# 10X_SD_CARD_READER_SCH_SHEET_3.net
KiCad netlist of a schematic drawn in Altium Designer
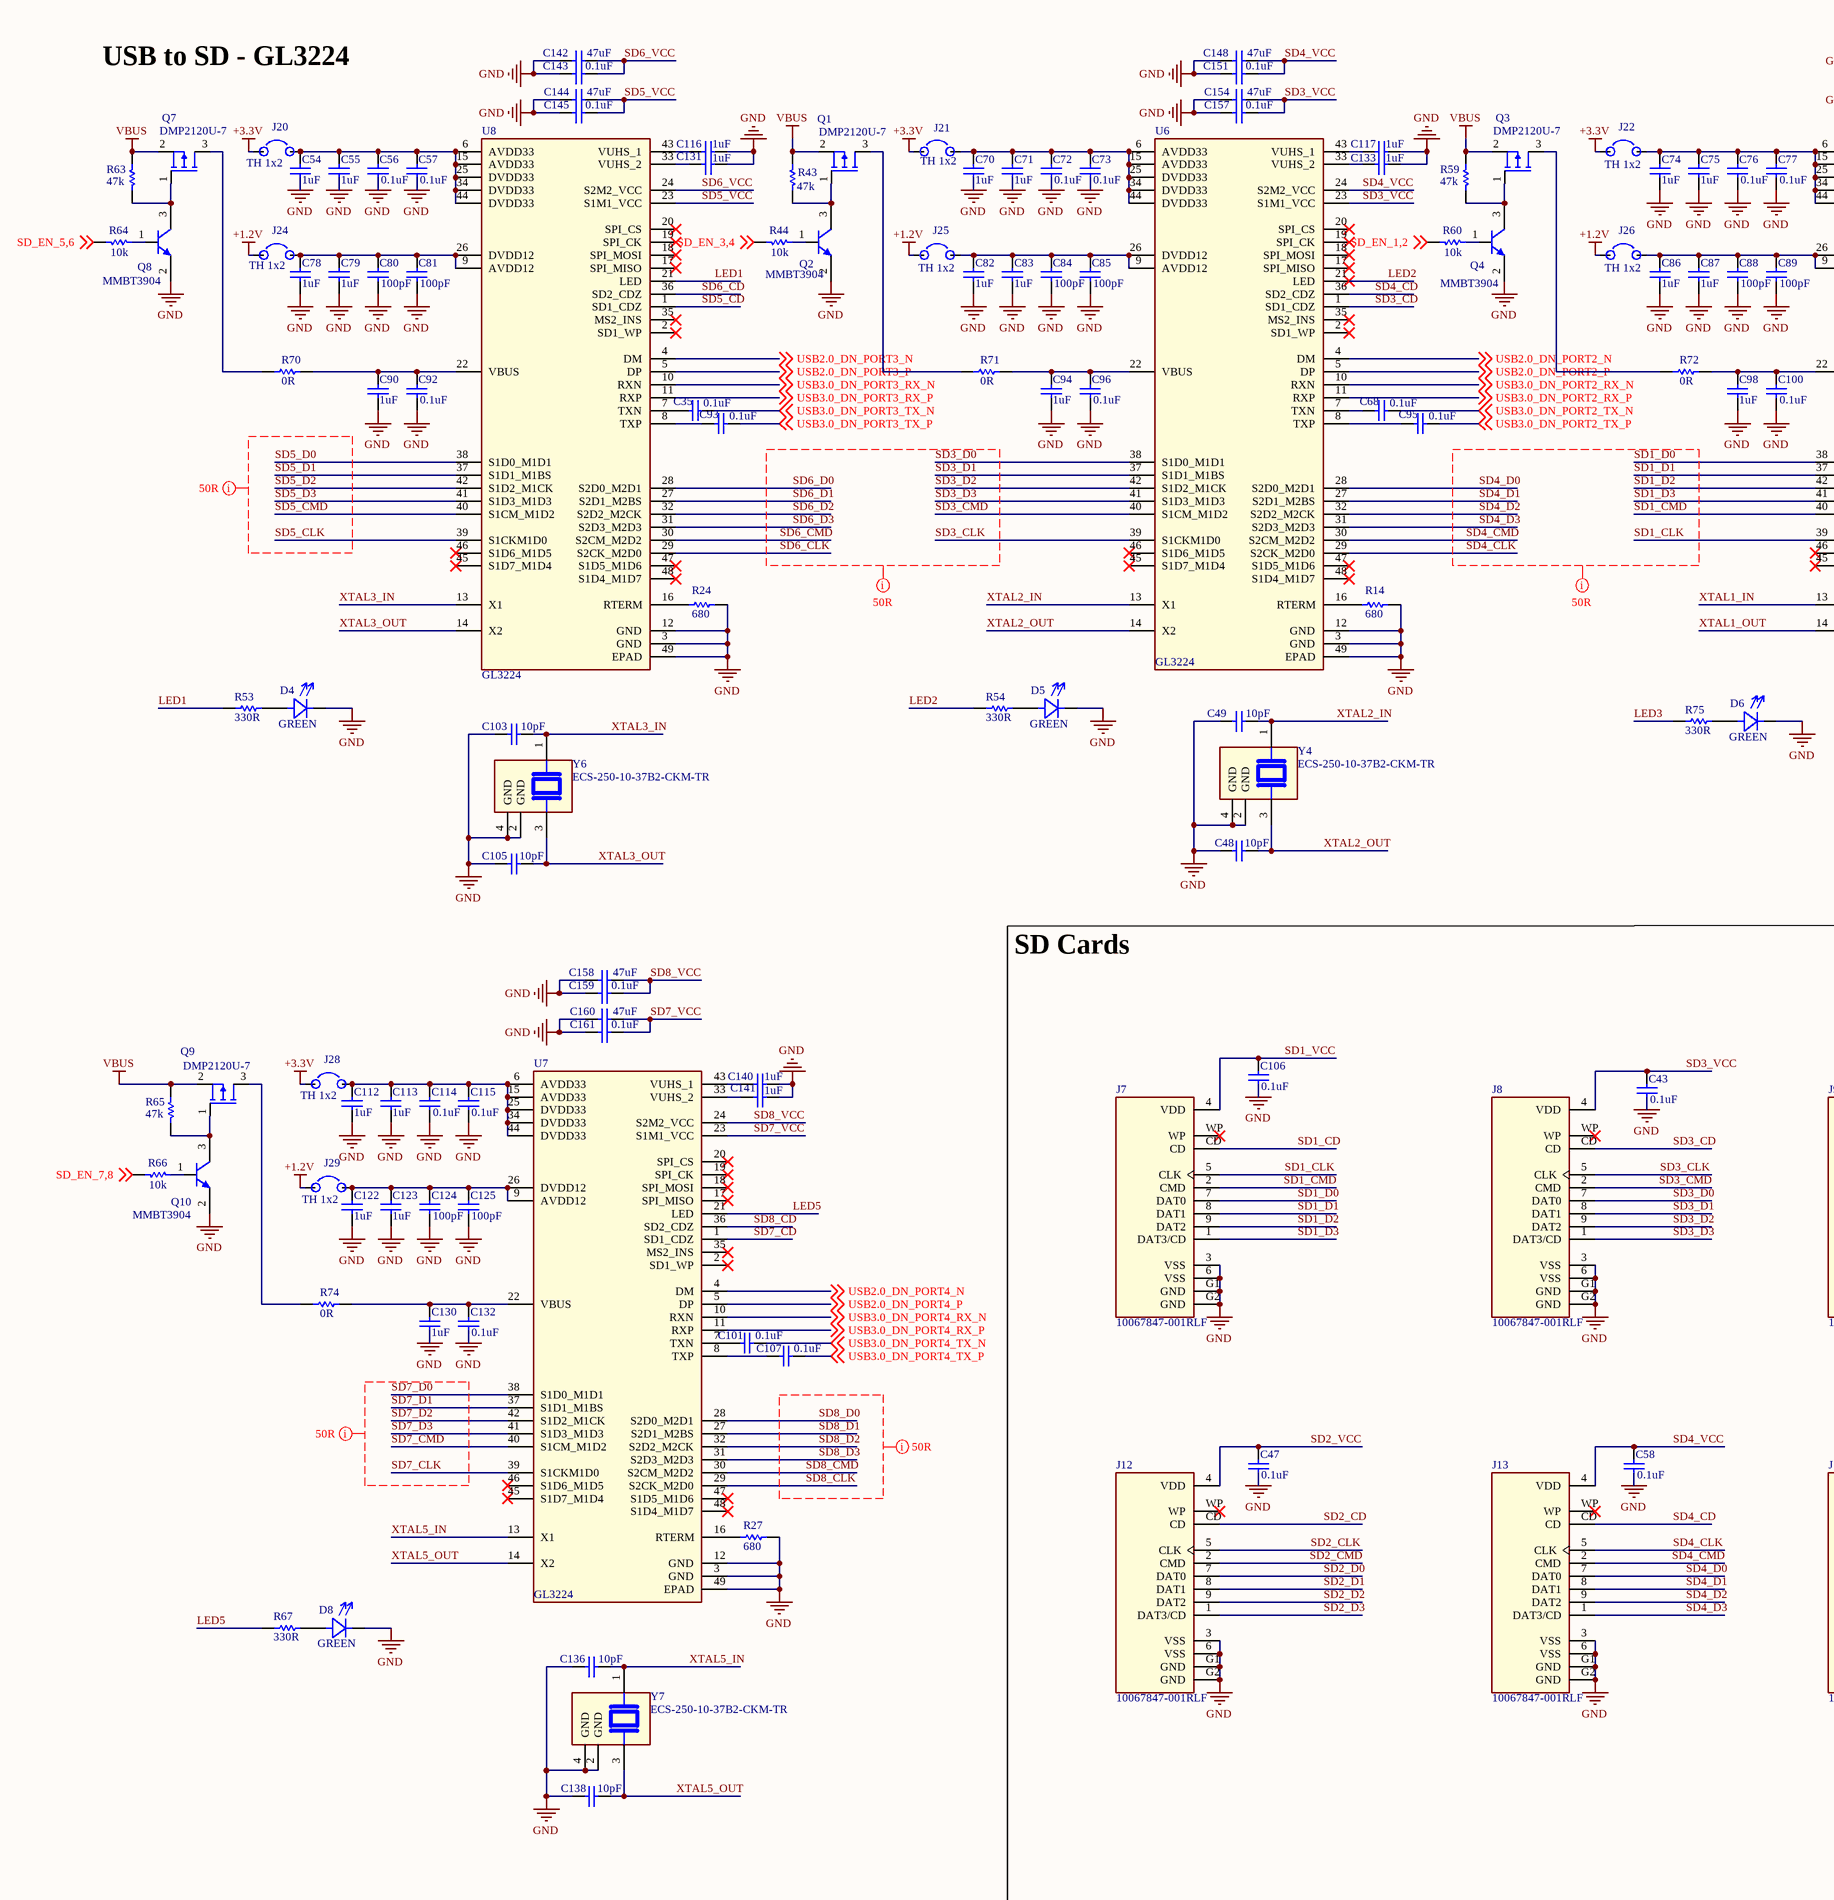
[diagram p0: 10X SD CARD READER SCH SHEET 3.SchDoc, left]
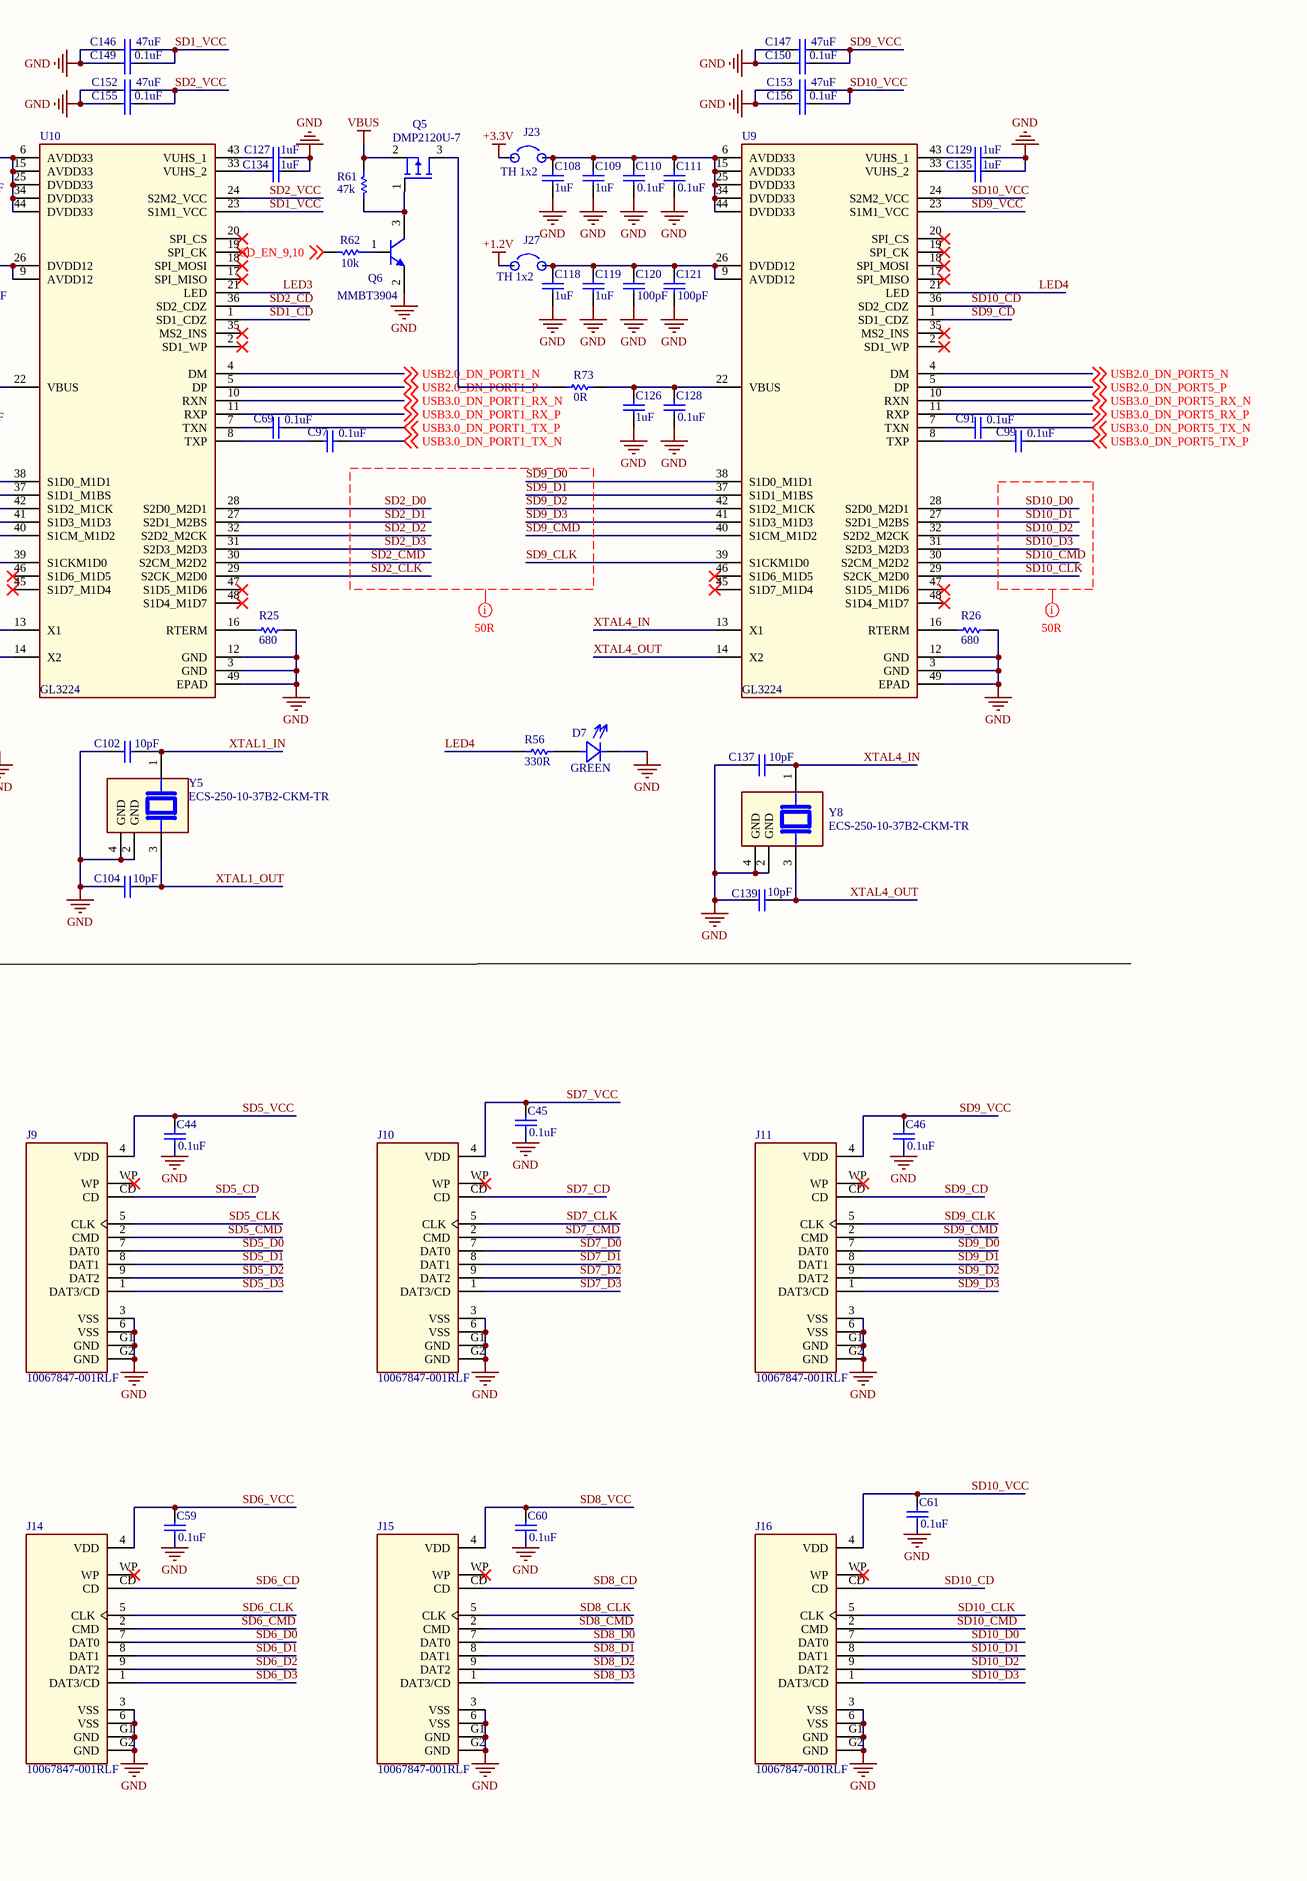
[diagram p1: 10X SD CARD READER SCH SHEET 3.SchDoc, right]

(export (version "E")
  (design (tool "Eeschema 10.0.6"))
  (components
    (comp (ref "C35")
      (value "0.1uF")
      (footprint "C-0402/1005")
      (description "Capacitor")
      (fields (field (name "PUBLISHER") "Altium Limited"))
      (libsource (lib "Miscellaneous Devices") (part "Cap"))
    )
    (comp (ref "C43")
      (value "0.1uF")
      (footprint "C-0402/1005")
      (description "Capacitor")
      (fields (field (name "PUBLISHER") "Altium Limited"))
      (libsource (lib "Miscellaneous Devices") (part "Cap"))
    )
    (comp (ref "C44")
      (value "0.1uF")
      (footprint "C-0402/1005")
      (description "Capacitor")
      (fields (field (name "PUBLISHER") "Altium Limited"))
      (libsource (lib "Miscellaneous Devices") (part "Cap"))
    )
    (comp (ref "C45")
      (value "0.1uF")
      (footprint "C-0402/1005")
      (description "Capacitor")
      (fields (field (name "PUBLISHER") "Altium Limited"))
      (libsource (lib "Miscellaneous Devices") (part "Cap"))
    )
    (comp (ref "C46")
      (value "0.1uF")
      (footprint "C-0402/1005")
      (description "Capacitor")
      (fields (field (name "PUBLISHER") "Altium Limited"))
      (libsource (lib "Miscellaneous Devices") (part "Cap"))
    )
    (comp (ref "C47")
      (value "0.1uF")
      (footprint "C-0402/1005")
      (description "Capacitor")
      (fields (field (name "PUBLISHER") "Altium Limited"))
      (libsource (lib "Miscellaneous Devices") (part "Cap"))
    )
    (comp (ref "C48")
      (value "10pF")
      (footprint "C-0402/1005")
      (description "Capacitor")
      (fields (field (name "PUBLISHER") "Altium Limited"))
      (libsource (lib "Miscellaneous Devices") (part "Cap"))
    )
    (comp (ref "C49")
      (value "10pF")
      (footprint "C-0402/1005")
      (description "Capacitor")
      (fields (field (name "PUBLISHER") "Altium Limited"))
      (libsource (lib "Miscellaneous Devices") (part "Cap"))
    )
    (comp (ref "C54")
      (value "1uF")
      (footprint "C-0402/1005")
      (description "Capacitor")
      (fields (field (name "PUBLISHER") "Altium Limited"))
      (libsource (lib "Miscellaneous Devices") (part "Cap"))
    )
    (comp (ref "C55")
      (value "1uF")
      (footprint "C-0402/1005")
      (description "Capacitor")
      (fields (field (name "PUBLISHER") "Altium Limited"))
      (libsource (lib "Miscellaneous Devices") (part "Cap"))
    )
    (comp (ref "C56")
      (value "0.1uF")
      (footprint "C-0402/1005")
      (description "Capacitor")
      (fields (field (name "PUBLISHER") "Altium Limited"))
      (libsource (lib "Miscellaneous Devices") (part "Cap"))
    )
    (comp (ref "C57")
      (value "0.1uF")
      (footprint "C-0402/1005")
      (description "Capacitor")
      (fields (field (name "PUBLISHER") "Altium Limited"))
      (libsource (lib "Miscellaneous Devices") (part "Cap"))
    )
    (comp (ref "C58")
      (value "0.1uF")
      (footprint "C-0402/1005")
      (description "Capacitor")
      (fields (field (name "PUBLISHER") "Altium Limited"))
      (libsource (lib "Miscellaneous Devices") (part "Cap"))
    )
    (comp (ref "C59")
      (value "0.1uF")
      (footprint "C-0402/1005")
      (description "Capacitor")
      (fields (field (name "PUBLISHER") "Altium Limited"))
      (libsource (lib "Miscellaneous Devices") (part "Cap"))
    )
    (comp (ref "C60")
      (value "0.1uF")
      (footprint "C-0402/1005")
      (description "Capacitor")
      (fields (field (name "PUBLISHER") "Altium Limited"))
      (libsource (lib "Miscellaneous Devices") (part "Cap"))
    )
    (comp (ref "C61")
      (value "0.1uF")
      (footprint "C-0402/1005")
      (description "Capacitor")
      (fields (field (name "PUBLISHER") "Altium Limited"))
      (libsource (lib "Miscellaneous Devices") (part "Cap"))
    )
    (comp (ref "C68")
      (value "0.1uF")
      (footprint "C-0402/1005")
      (description "Capacitor")
      (fields (field (name "PUBLISHER") "Altium Limited"))
      (libsource (lib "Miscellaneous Devices") (part "Cap"))
    )
    (comp (ref "C69")
      (value "0.1uF")
      (footprint "C-0402/1005")
      (description "Capacitor")
      (fields (field (name "PUBLISHER") "Altium Limited"))
      (libsource (lib "Miscellaneous Devices") (part "Cap"))
    )
    (comp (ref "C70")
      (value "1uF")
      (footprint "C-0402/1005")
      (description "Capacitor")
      (fields (field (name "PUBLISHER") "Altium Limited"))
      (libsource (lib "Miscellaneous Devices") (part "Cap"))
    )
    (comp (ref "C71")
      (value "1uF")
      (footprint "C-0402/1005")
      (description "Capacitor")
      (fields (field (name "PUBLISHER") "Altium Limited"))
      (libsource (lib "Miscellaneous Devices") (part "Cap"))
    )
    (comp (ref "C72")
      (value "0.1uF")
      (footprint "C-0402/1005")
      (description "Capacitor")
      (fields (field (name "PUBLISHER") "Altium Limited"))
      (libsource (lib "Miscellaneous Devices") (part "Cap"))
    )
    (comp (ref "C73")
      (value "0.1uF")
      (footprint "C-0402/1005")
      (description "Capacitor")
      (fields (field (name "PUBLISHER") "Altium Limited"))
      (libsource (lib "Miscellaneous Devices") (part "Cap"))
    )
    (comp (ref "C74")
      (value "1uF")
      (footprint "C-0402/1005")
      (description "Capacitor")
      (fields (field (name "PUBLISHER") "Altium Limited"))
      (libsource (lib "Miscellaneous Devices") (part "Cap"))
    )
    (comp (ref "C75")
      (value "1uF")
      (footprint "C-0402/1005")
      (description "Capacitor")
      (fields (field (name "PUBLISHER") "Altium Limited"))
      (libsource (lib "Miscellaneous Devices") (part "Cap"))
    )
    (comp (ref "C76")
      (value "0.1uF")
      (footprint "C-0402/1005")
      (description "Capacitor")
      (fields (field (name "PUBLISHER") "Altium Limited"))
      (libsource (lib "Miscellaneous Devices") (part "Cap"))
    )
    (comp (ref "C77")
      (value "0.1uF")
      (footprint "C-0402/1005")
      (description "Capacitor")
      (fields (field (name "PUBLISHER") "Altium Limited"))
      (libsource (lib "Miscellaneous Devices") (part "Cap"))
    )
    (comp (ref "C78")
      (value "1uF")
      (footprint "C-0402/1005")
      (description "Capacitor")
      (fields (field (name "PUBLISHER") "Altium Limited"))
      (libsource (lib "Miscellaneous Devices") (part "Cap"))
    )
    (comp (ref "C79")
      (value "1uF")
      (footprint "C-0402/1005")
      (description "Capacitor")
      (fields (field (name "PUBLISHER") "Altium Limited"))
      (libsource (lib "Miscellaneous Devices") (part "Cap"))
    )
    (comp (ref "C80")
      (value "100pF")
      (footprint "C-0402/1005")
      (description "Capacitor")
      (fields (field (name "Comment") "0.1uF") (field (name "PUBLISHER") "Altium Limited"))
      (libsource (lib "Miscellaneous Devices") (part "Cap"))
    )
    (comp (ref "C81")
      (value "100pF")
      (footprint "C-0402/1005")
      (description "Capacitor")
      (fields (field (name "Comment") "0.1uF") (field (name "PUBLISHER") "Altium Limited"))
      (libsource (lib "Miscellaneous Devices") (part "Cap"))
    )
    (comp (ref "C82")
      (value "1uF")
      (footprint "C-0402/1005")
      (description "Capacitor")
      (fields (field (name "PUBLISHER") "Altium Limited"))
      (libsource (lib "Miscellaneous Devices") (part "Cap"))
    )
    (comp (ref "C83")
      (value "1uF")
      (footprint "C-0402/1005")
      (description "Capacitor")
      (fields (field (name "PUBLISHER") "Altium Limited"))
      (libsource (lib "Miscellaneous Devices") (part "Cap"))
    )
    (comp (ref "C84")
      (value "100pF")
      (footprint "C-0402/1005")
      (description "Capacitor")
      (fields (field (name "Comment") "0.1uF") (field (name "PUBLISHER") "Altium Limited"))
      (libsource (lib "Miscellaneous Devices") (part "Cap"))
    )
    (comp (ref "C85")
      (value "100pF")
      (footprint "C-0402/1005")
      (description "Capacitor")
      (fields (field (name "Comment") "0.1uF") (field (name "PUBLISHER") "Altium Limited"))
      (libsource (lib "Miscellaneous Devices") (part "Cap"))
    )
    (comp (ref "C86")
      (value "1uF")
      (footprint "C-0402/1005")
      (description "Capacitor")
      (fields (field (name "PUBLISHER") "Altium Limited"))
      (libsource (lib "Miscellaneous Devices") (part "Cap"))
    )
    (comp (ref "C87")
      (value "1uF")
      (footprint "C-0402/1005")
      (description "Capacitor")
      (fields (field (name "PUBLISHER") "Altium Limited"))
      (libsource (lib "Miscellaneous Devices") (part "Cap"))
    )
    (comp (ref "C88")
      (value "100pF")
      (footprint "C-0402/1005")
      (description "Capacitor")
      (fields (field (name "Comment") "0.1uF") (field (name "PUBLISHER") "Altium Limited"))
      (libsource (lib "Miscellaneous Devices") (part "Cap"))
    )
    (comp (ref "C89")
      (value "100pF")
      (footprint "C-0402/1005")
      (description "Capacitor")
      (fields (field (name "Comment") "0.1uF") (field (name "PUBLISHER") "Altium Limited"))
      (libsource (lib "Miscellaneous Devices") (part "Cap"))
    )
    (comp (ref "C90")
      (value "1uF")
      (footprint "C-0402/1005")
      (description "Capacitor")
      (fields (field (name "PUBLISHER") "Altium Limited"))
      (libsource (lib "Miscellaneous Devices") (part "Cap"))
    )
    (comp (ref "C91")
      (value "0.1uF")
      (footprint "C-0402/1005")
      (description "Capacitor")
      (fields (field (name "PUBLISHER") "Altium Limited"))
      (libsource (lib "Miscellaneous Devices") (part "Cap"))
    )
    (comp (ref "C92")
      (value "0.1uF")
      (footprint "C-0402/1005")
      (description "Capacitor")
      (fields (field (name "PUBLISHER") "Altium Limited"))
      (libsource (lib "Miscellaneous Devices") (part "Cap"))
    )
    (comp (ref "C93")
      (value "0.1uF")
      (footprint "C-0402/1005")
      (description "Capacitor")
      (fields (field (name "PUBLISHER") "Altium Limited"))
      (libsource (lib "Miscellaneous Devices") (part "Cap"))
    )
    (comp (ref "C94")
      (value "1uF")
      (footprint "C-0402/1005")
      (description "Capacitor")
      (fields (field (name "PUBLISHER") "Altium Limited"))
      (libsource (lib "Miscellaneous Devices") (part "Cap"))
    )
    (comp (ref "C95")
      (value "0.1uF")
      (footprint "C-0402/1005")
      (description "Capacitor")
      (fields (field (name "PUBLISHER") "Altium Limited"))
      (libsource (lib "Miscellaneous Devices") (part "Cap"))
    )
    (comp (ref "C96")
      (value "0.1uF")
      (footprint "C-0402/1005")
      (description "Capacitor")
      (fields (field (name "PUBLISHER") "Altium Limited"))
      (libsource (lib "Miscellaneous Devices") (part "Cap"))
    )
    (comp (ref "C97")
      (value "0.1uF")
      (footprint "C-0402/1005")
      (description "Capacitor")
      (fields (field (name "PUBLISHER") "Altium Limited"))
      (libsource (lib "Miscellaneous Devices") (part "Cap"))
    )
    (comp (ref "C98")
      (value "1uF")
      (footprint "C-0402/1005")
      (description "Capacitor")
      (fields (field (name "PUBLISHER") "Altium Limited"))
      (libsource (lib "Miscellaneous Devices") (part "Cap"))
    )
    (comp (ref "C99")
      (value "0.1uF")
      (footprint "C-0402/1005")
      (description "Capacitor")
      (fields (field (name "PUBLISHER") "Altium Limited"))
      (libsource (lib "Miscellaneous Devices") (part "Cap"))
    )
    (comp (ref "C100")
      (value "0.1uF")
      (footprint "C-0402/1005")
      (description "Capacitor")
      (fields (field (name "PUBLISHER") "Altium Limited"))
      (libsource (lib "Miscellaneous Devices") (part "Cap"))
    )
    (comp (ref "C101")
      (value "0.1uF")
      (footprint "C-0402/1005")
      (description "Capacitor")
      (fields (field (name "PUBLISHER") "Altium Limited"))
      (libsource (lib "Miscellaneous Devices") (part "Cap"))
    )
    (comp (ref "C102")
      (value "10pF")
      (footprint "C-0402/1005")
      (description "Capacitor")
      (fields (field (name "PUBLISHER") "Altium Limited"))
      (libsource (lib "Miscellaneous Devices") (part "Cap"))
    )
    (comp (ref "C103")
      (value "10pF")
      (footprint "C-0402/1005")
      (description "Capacitor")
      (fields (field (name "PUBLISHER") "Altium Limited"))
      (libsource (lib "Miscellaneous Devices") (part "Cap"))
    )
    (comp (ref "C104")
      (value "10pF")
      (footprint "C-0402/1005")
      (description "Capacitor")
      (fields (field (name "PUBLISHER") "Altium Limited"))
      (libsource (lib "Miscellaneous Devices") (part "Cap"))
    )
    (comp (ref "C105")
      (value "10pF")
      (footprint "C-0402/1005")
      (description "Capacitor")
      (fields (field (name "PUBLISHER") "Altium Limited"))
      (libsource (lib "Miscellaneous Devices") (part "Cap"))
    )
    (comp (ref "C106")
      (value "0.1uF")
      (footprint "C-0402/1005")
      (description "Capacitor")
      (fields (field (name "PUBLISHER") "Altium Limited"))
      (libsource (lib "Miscellaneous Devices") (part "Cap"))
    )
    (comp (ref "C107")
      (value "0.1uF")
      (footprint "C-0402/1005")
      (description "Capacitor")
      (fields (field (name "PUBLISHER") "Altium Limited"))
      (libsource (lib "Miscellaneous Devices") (part "Cap"))
    )
    (comp (ref "C108")
      (value "1uF")
      (footprint "C-0402/1005")
      (description "Capacitor")
      (fields (field (name "PUBLISHER") "Altium Limited"))
      (libsource (lib "Miscellaneous Devices") (part "Cap"))
    )
    (comp (ref "C109")
      (value "1uF")
      (footprint "C-0402/1005")
      (description "Capacitor")
      (fields (field (name "PUBLISHER") "Altium Limited"))
      (libsource (lib "Miscellaneous Devices") (part "Cap"))
    )
    (comp (ref "C110")
      (value "0.1uF")
      (footprint "C-0402/1005")
      (description "Capacitor")
      (fields (field (name "PUBLISHER") "Altium Limited"))
      (libsource (lib "Miscellaneous Devices") (part "Cap"))
    )
    (comp (ref "C111")
      (value "0.1uF")
      (footprint "C-0402/1005")
      (description "Capacitor")
      (fields (field (name "PUBLISHER") "Altium Limited"))
      (libsource (lib "Miscellaneous Devices") (part "Cap"))
    )
    (comp (ref "C112")
      (value "1uF")
      (footprint "C-0402/1005")
      (description "Capacitor")
      (fields (field (name "PUBLISHER") "Altium Limited"))
      (libsource (lib "Miscellaneous Devices") (part "Cap"))
    )
    (comp (ref "C113")
      (value "1uF")
      (footprint "C-0402/1005")
      (description "Capacitor")
      (fields (field (name "PUBLISHER") "Altium Limited"))
      (libsource (lib "Miscellaneous Devices") (part "Cap"))
    )
    (comp (ref "C114")
      (value "0.1uF")
      (footprint "C-0402/1005")
      (description "Capacitor")
      (fields (field (name "PUBLISHER") "Altium Limited"))
      (libsource (lib "Miscellaneous Devices") (part "Cap"))
    )
    (comp (ref "C115")
      (value "0.1uF")
      (footprint "C-0402/1005")
      (description "Capacitor")
      (fields (field (name "PUBLISHER") "Altium Limited"))
      (libsource (lib "Miscellaneous Devices") (part "Cap"))
    )
    (comp (ref "C116")
      (value "1uF")
      (footprint "C-0402/1005")
      (description "Capacitor")
      (fields (field (name "PUBLISHER") "Altium Limited"))
      (libsource (lib "Miscellaneous Devices") (part "Cap"))
    )
    (comp (ref "C117")
      (value "1uF")
      (footprint "C-0402/1005")
      (description "Capacitor")
      (fields (field (name "PUBLISHER") "Altium Limited"))
      (libsource (lib "Miscellaneous Devices") (part "Cap"))
    )
    (comp (ref "C118")
      (value "1uF")
      (footprint "C-0402/1005")
      (description "Capacitor")
      (fields (field (name "PUBLISHER") "Altium Limited"))
      (libsource (lib "Miscellaneous Devices") (part "Cap"))
    )
    (comp (ref "C119")
      (value "1uF")
      (footprint "C-0402/1005")
      (description "Capacitor")
      (fields (field (name "PUBLISHER") "Altium Limited"))
      (libsource (lib "Miscellaneous Devices") (part "Cap"))
    )
    (comp (ref "C120")
      (value "100pF")
      (footprint "C-0402/1005")
      (description "Capacitor")
      (fields (field (name "Comment") "0.1uF") (field (name "PUBLISHER") "Altium Limited"))
      (libsource (lib "Miscellaneous Devices") (part "Cap"))
    )
    (comp (ref "C121")
      (value "100pF")
      (footprint "C-0402/1005")
      (description "Capacitor")
      (fields (field (name "Comment") "0.1uF") (field (name "PUBLISHER") "Altium Limited"))
      (libsource (lib "Miscellaneous Devices") (part "Cap"))
    )
    (comp (ref "C122")
      (value "1uF")
      (footprint "C-0402/1005")
      (description "Capacitor")
      (fields (field (name "PUBLISHER") "Altium Limited"))
      (libsource (lib "Miscellaneous Devices") (part "Cap"))
    )
    (comp (ref "C123")
      (value "1uF")
      (footprint "C-0402/1005")
      (description "Capacitor")
      (fields (field (name "PUBLISHER") "Altium Limited"))
      (libsource (lib "Miscellaneous Devices") (part "Cap"))
    )
    (comp (ref "C124")
      (value "100pF")
      (footprint "C-0402/1005")
      (description "Capacitor")
      (fields (field (name "Comment") "0.1uF") (field (name "PUBLISHER") "Altium Limited"))
      (libsource (lib "Miscellaneous Devices") (part "Cap"))
    )
    (comp (ref "C125")
      (value "100pF")
      (footprint "C-0402/1005")
      (description "Capacitor")
      (fields (field (name "Comment") "0.1uF") (field (name "PUBLISHER") "Altium Limited"))
      (libsource (lib "Miscellaneous Devices") (part "Cap"))
    )
    (comp (ref "C126")
      (value "1uF")
      (footprint "C-0402/1005")
      (description "Capacitor")
      (fields (field (name "PUBLISHER") "Altium Limited"))
      (libsource (lib "Miscellaneous Devices") (part "Cap"))
    )
    (comp (ref "C127")
      (value "1uF")
      (footprint "C-0402/1005")
      (description "Capacitor")
      (fields (field (name "PUBLISHER") "Altium Limited"))
      (libsource (lib "Miscellaneous Devices") (part "Cap"))
    )
    (comp (ref "C128")
      (value "0.1uF")
      (footprint "C-0402/1005")
      (description "Capacitor")
      (fields (field (name "PUBLISHER") "Altium Limited"))
      (libsource (lib "Miscellaneous Devices") (part "Cap"))
    )
    (comp (ref "C129")
      (value "1uF")
      (footprint "C-0402/1005")
      (description "Capacitor")
      (fields (field (name "PUBLISHER") "Altium Limited"))
      (libsource (lib "Miscellaneous Devices") (part "Cap"))
    )
    (comp (ref "C130")
      (value "1uF")
      (footprint "C-0402/1005")
      (description "Capacitor")
      (fields (field (name "PUBLISHER") "Altium Limited"))
      (libsource (lib "Miscellaneous Devices") (part "Cap"))
    )
    (comp (ref "C131")
      (value "1uF")
      (footprint "C-0402/1005")
      (description "Capacitor")
      (fields (field (name "PUBLISHER") "Altium Limited"))
      (libsource (lib "Miscellaneous Devices") (part "Cap"))
    )
    (comp (ref "C132")
      (value "0.1uF")
      (footprint "C-0402/1005")
      (description "Capacitor")
      (fields (field (name "PUBLISHER") "Altium Limited"))
      (libsource (lib "Miscellaneous Devices") (part "Cap"))
    )
    (comp (ref "C133")
      (value "1uF")
      (footprint "C-0402/1005")
      (description "Capacitor")
      (fields (field (name "PUBLISHER") "Altium Limited"))
      (libsource (lib "Miscellaneous Devices") (part "Cap"))
    )
    (comp (ref "C134")
      (value "1uF")
      (footprint "C-0402/1005")
      (description "Capacitor")
      (fields (field (name "PUBLISHER") "Altium Limited"))
      (libsource (lib "Miscellaneous Devices") (part "Cap"))
    )
    (comp (ref "C135")
      (value "1uF")
      (footprint "C-0402/1005")
      (description "Capacitor")
      (fields (field (name "PUBLISHER") "Altium Limited"))
      (libsource (lib "Miscellaneous Devices") (part "Cap"))
    )
    (comp (ref "C136")
      (value "10pF")
      (footprint "C-0402/1005")
      (description "Capacitor")
      (fields (field (name "PUBLISHER") "Altium Limited"))
      (libsource (lib "Miscellaneous Devices") (part "Cap"))
    )
    (comp (ref "C137")
      (value "10pF")
      (footprint "C-0402/1005")
      (description "Capacitor")
      (fields (field (name "PUBLISHER") "Altium Limited"))
      (libsource (lib "Miscellaneous Devices") (part "Cap"))
    )
    (comp (ref "C138")
      (value "10pF")
      (footprint "C-0402/1005")
      (description "Capacitor")
      (fields (field (name "PUBLISHER") "Altium Limited"))
      (libsource (lib "Miscellaneous Devices") (part "Cap"))
    )
    (comp (ref "C139")
      (value "10pF")
      (footprint "C-0402/1005")
      (description "Capacitor")
      (fields (field (name "PUBLISHER") "Altium Limited"))
      (libsource (lib "Miscellaneous Devices") (part "Cap"))
    )
    (comp (ref "C140")
      (value "1uF")
      (footprint "C-0402/1005")
      (description "Capacitor")
      (fields (field (name "PUBLISHER") "Altium Limited"))
      (libsource (lib "Miscellaneous Devices") (part "Cap"))
    )
    (comp (ref "C141")
      (value "1uF")
      (footprint "C-0402/1005")
      (description "Capacitor")
      (fields (field (name "PUBLISHER") "Altium Limited"))
      (libsource (lib "Miscellaneous Devices") (part "Cap"))
    )
    (comp (ref "C142")
      (value "47uF")
      (footprint "C-0603/1608")
      (description "Capacitor")
      (fields (field (name "Comment") "0.1uF") (field (name "PUBLISHER") "Altium Limited"))
      (libsource (lib "Miscellaneous Devices") (part "Cap"))
    )
    (comp (ref "C143")
      (value "0.1uF")
      (footprint "C-0402/1005")
      (description "Capacitor")
      (fields (field (name "PUBLISHER") "Altium Limited"))
      (libsource (lib "Miscellaneous Devices") (part "Cap"))
    )
    (comp (ref "C144")
      (value "47uF")
      (footprint "C-0603/1608")
      (description "Capacitor")
      (fields (field (name "Comment") "0.1uF") (field (name "PUBLISHER") "Altium Limited"))
      (libsource (lib "Miscellaneous Devices") (part "Cap"))
    )
    (comp (ref "C145")
      (value "0.1uF")
      (footprint "C-0402/1005")
      (description "Capacitor")
      (fields (field (name "PUBLISHER") "Altium Limited"))
      (libsource (lib "Miscellaneous Devices") (part "Cap"))
    )
    (comp (ref "C146")
      (value "47uF")
      (footprint "C-0603/1608")
      (description "Capacitor")
      (fields (field (name "Comment") "0.1uF") (field (name "PUBLISHER") "Altium Limited"))
      (libsource (lib "Miscellaneous Devices") (part "Cap"))
    )
    (comp (ref "C147")
      (value "47uF")
      (footprint "C-0603/1608")
      (description "Capacitor")
      (fields (field (name "Comment") "0.1uF") (field (name "PUBLISHER") "Altium Limited"))
      (libsource (lib "Miscellaneous Devices") (part "Cap"))
    )
    (comp (ref "C148")
      (value "47uF")
      (footprint "C-0603/1608")
      (description "Capacitor")
      (fields (field (name "Comment") "0.1uF") (field (name "PUBLISHER") "Altium Limited"))
      (libsource (lib "Miscellaneous Devices") (part "Cap"))
    )
    (comp (ref "C149")
      (value "0.1uF")
      (footprint "C-0402/1005")
      (description "Capacitor")
      (fields (field (name "PUBLISHER") "Altium Limited"))
      (libsource (lib "Miscellaneous Devices") (part "Cap"))
    )
    (comp (ref "C150")
      (value "0.1uF")
      (footprint "C-0402/1005")
      (description "Capacitor")
      (fields (field (name "PUBLISHER") "Altium Limited"))
      (libsource (lib "Miscellaneous Devices") (part "Cap"))
    )
    (comp (ref "C151")
      (value "0.1uF")
      (footprint "C-0402/1005")
      (description "Capacitor")
      (fields (field (name "PUBLISHER") "Altium Limited"))
      (libsource (lib "Miscellaneous Devices") (part "Cap"))
    )
    (comp (ref "C152")
      (value "47uF")
      (footprint "C-0603/1608")
      (description "Capacitor")
      (fields (field (name "Comment") "0.1uF") (field (name "PUBLISHER") "Altium Limited"))
      (libsource (lib "Miscellaneous Devices") (part "Cap"))
    )
    (comp (ref "C153")
      (value "47uF")
      (footprint "C-0603/1608")
      (description "Capacitor")
      (fields (field (name "Comment") "0.1uF") (field (name "PUBLISHER") "Altium Limited"))
      (libsource (lib "Miscellaneous Devices") (part "Cap"))
    )
    (comp (ref "C154")
      (value "47uF")
      (footprint "C-0603/1608")
      (description "Capacitor")
      (fields (field (name "Comment") "0.1uF") (field (name "PUBLISHER") "Altium Limited"))
      (libsource (lib "Miscellaneous Devices") (part "Cap"))
    )
    (comp (ref "C155")
      (value "0.1uF")
      (footprint "C-0402/1005")
      (description "Capacitor")
      (fields (field (name "PUBLISHER") "Altium Limited"))
      (libsource (lib "Miscellaneous Devices") (part "Cap"))
    )
    (comp (ref "C156")
      (value "0.1uF")
      (footprint "C-0402/1005")
      (description "Capacitor")
      (fields (field (name "PUBLISHER") "Altium Limited"))
      (libsource (lib "Miscellaneous Devices") (part "Cap"))
    )
    (comp (ref "C157")
      (value "0.1uF")
      (footprint "C-0402/1005")
      (description "Capacitor")
      (fields (field (name "PUBLISHER") "Altium Limited"))
      (libsource (lib "Miscellaneous Devices") (part "Cap"))
    )
    (comp (ref "C158")
      (value "47uF")
      (footprint "C-0603/1608")
      (description "Capacitor")
      (fields (field (name "Comment") "0.1uF") (field (name "PUBLISHER") "Altium Limited"))
      (libsource (lib "Miscellaneous Devices") (part "Cap"))
    )
    (comp (ref "C159")
      (value "0.1uF")
      (footprint "C-0402/1005")
      (description "Capacitor")
      (fields (field (name "PUBLISHER") "Altium Limited"))
      (libsource (lib "Miscellaneous Devices") (part "Cap"))
    )
    (comp (ref "C160")
      (value "47uF")
      (footprint "C-0603/1608")
      (description "Capacitor")
      (fields (field (name "Comment") "0.1uF") (field (name "PUBLISHER") "Altium Limited"))
      (libsource (lib "Miscellaneous Devices") (part "Cap"))
    )
    (comp (ref "C161")
      (value "0.1uF")
      (footprint "C-0402/1005")
      (description "Capacitor")
      (fields (field (name "PUBLISHER") "Altium Limited"))
      (libsource (lib "Miscellaneous Devices") (part "Cap"))
    )
    (comp (ref "D4")
      (value "GREEN")
      (footprint "LEDC1608X65N")
      (libsource (lib "Custom_Library") (part "Diode-LED"))
    )
    (comp (ref "D5")
      (value "GREEN")
      (footprint "LEDC1608X65N")
      (libsource (lib "Custom_Library") (part "Diode-LED"))
    )
    (comp (ref "D6")
      (value "GREEN")
      (footprint "LEDC1608X65N")
      (libsource (lib "Custom_Library") (part "Diode-LED"))
    )
    (comp (ref "D7")
      (value "GREEN")
      (footprint "LEDC1608X65N")
      (libsource (lib "Custom_Library") (part "Diode-LED"))
    )
    (comp (ref "D8")
      (value "GREEN")
      (footprint "LEDC1608X65N")
      (libsource (lib "Custom_Library") (part "Diode-LED"))
    )
    (comp (ref "J7")
      (value "10067847-001RLF")
      (footprint "AMPHENOL_10067847-011RLF")
      (description "12 (9 + 3) Position Card Connector Secure Digital - SD Surface Mount Gold")
      (fields (field (name "DIGI-KEY_PART_NUMBER") "609-3956-1-ND") (field (name "MF") "Amphenol ICC"))
      (libsource (lib "10067847-001RLF") (part "10067847-001RLF"))
    )
    (comp (ref "J8")
      (value "10067847-001RLF")
      (footprint "AMPHENOL_10067847-011RLF")
      (description "12 (9 + 3) Position Card Connector Secure Digital - SD Surface Mount Gold")
      (fields (field (name "DIGI-KEY_PART_NUMBER") "609-3956-1-ND") (field (name "MF") "Amphenol ICC"))
      (libsource (lib "10067847-001RLF") (part "10067847-001RLF"))
    )
    (comp (ref "J9")
      (value "10067847-001RLF")
      (footprint "AMPHENOL_10067847-011RLF")
      (description "12 (9 + 3) Position Card Connector Secure Digital - SD Surface Mount Gold")
      (fields (field (name "DIGI-KEY_PART_NUMBER") "609-3956-1-ND") (field (name "MF") "Amphenol ICC"))
      (libsource (lib "10067847-001RLF") (part "10067847-001RLF"))
    )
    (comp (ref "J10")
      (value "10067847-001RLF")
      (footprint "AMPHENOL_10067847-011RLF")
      (description "12 (9 + 3) Position Card Connector Secure Digital - SD Surface Mount Gold")
      (fields (field (name "DIGI-KEY_PART_NUMBER") "609-3956-1-ND") (field (name "MF") "Amphenol ICC"))
      (libsource (lib "10067847-001RLF") (part "10067847-001RLF"))
    )
    (comp (ref "J11")
      (value "10067847-001RLF")
      (footprint "AMPHENOL_10067847-011RLF")
      (description "12 (9 + 3) Position Card Connector Secure Digital - SD Surface Mount Gold")
      (fields (field (name "DIGI-KEY_PART_NUMBER") "609-3956-1-ND") (field (name "MF") "Amphenol ICC"))
      (libsource (lib "10067847-001RLF") (part "10067847-001RLF"))
    )
    (comp (ref "J12")
      (value "10067847-001RLF")
      (footprint "AMPHENOL_10067847-011RLF")
      (description "12 (9 + 3) Position Card Connector Secure Digital - SD Surface Mount Gold")
      (fields (field (name "DIGI-KEY_PART_NUMBER") "609-3956-1-ND") (field (name "MF") "Amphenol ICC"))
      (libsource (lib "10067847-001RLF") (part "10067847-001RLF"))
    )
    (comp (ref "J13")
      (value "10067847-001RLF")
      (footprint "AMPHENOL_10067847-011RLF")
      (description "12 (9 + 3) Position Card Connector Secure Digital - SD Surface Mount Gold")
      (fields (field (name "DIGI-KEY_PART_NUMBER") "609-3956-1-ND") (field (name "MF") "Amphenol ICC"))
      (libsource (lib "10067847-001RLF") (part "10067847-001RLF"))
    )
    (comp (ref "J14")
      (value "10067847-001RLF")
      (footprint "AMPHENOL_10067847-011RLF")
      (description "12 (9 + 3) Position Card Connector Secure Digital - SD Surface Mount Gold")
      (fields (field (name "DIGI-KEY_PART_NUMBER") "609-3956-1-ND") (field (name "MF") "Amphenol ICC"))
      (libsource (lib "10067847-001RLF") (part "10067847-001RLF"))
    )
    (comp (ref "J15")
      (value "10067847-001RLF")
      (footprint "AMPHENOL_10067847-011RLF")
      (description "12 (9 + 3) Position Card Connector Secure Digital - SD Surface Mount Gold")
      (fields (field (name "DIGI-KEY_PART_NUMBER") "609-3956-1-ND") (field (name "MF") "Amphenol ICC"))
      (libsource (lib "10067847-001RLF") (part "10067847-001RLF"))
    )
    (comp (ref "J16")
      (value "10067847-001RLF")
      (footprint "AMPHENOL_10067847-011RLF")
      (description "12 (9 + 3) Position Card Connector Secure Digital - SD Surface Mount Gold")
      (fields (field (name "DIGI-KEY_PART_NUMBER") "609-3956-1-ND") (field (name "MF") "Amphenol ICC"))
      (libsource (lib "10067847-001RLF") (part "10067847-001RLF"))
    )
    (comp (ref "J20")
      (value "TH 1x2")
      (footprint "PIN HEADER 1x2 2.54mm")
      (description "CONN HEADER VERT 3POS 2.54MM")
      (fields (field (name "MFR. PART NO.") "75160-156-03LF"))
      (libsource (lib "Custom_Library") (part "Jumper 2 pin"))
    )
    (comp (ref "J21")
      (value "TH 1x2")
      (footprint "PIN HEADER 1x2 2.54mm")
      (description "CONN HEADER VERT 3POS 2.54MM")
      (fields (field (name "MFR. PART NO.") "75160-156-03LF"))
      (libsource (lib "Custom_Library") (part "Jumper 2 pin"))
    )
    (comp (ref "J22")
      (value "TH 1x2")
      (footprint "PIN HEADER 1x2 2.54mm")
      (description "CONN HEADER VERT 3POS 2.54MM")
      (fields (field (name "MFR. PART NO.") "75160-156-03LF"))
      (libsource (lib "Custom_Library") (part "Jumper 2 pin"))
    )
    (comp (ref "J23")
      (value "TH 1x2")
      (footprint "PIN HEADER 1x2 2.54mm")
      (description "CONN HEADER VERT 3POS 2.54MM")
      (fields (field (name "MFR. PART NO.") "75160-156-03LF"))
      (libsource (lib "Custom_Library") (part "Jumper 2 pin"))
    )
    (comp (ref "J24")
      (value "TH 1x2")
      (footprint "PIN HEADER 1x2 2.54mm")
      (description "CONN HEADER VERT 3POS 2.54MM")
      (fields (field (name "MFR. PART NO.") "75160-156-03LF"))
      (libsource (lib "Custom_Library") (part "Jumper 2 pin"))
    )
    (comp (ref "J25")
      (value "TH 1x2")
      (footprint "PIN HEADER 1x2 2.54mm")
      (description "CONN HEADER VERT 3POS 2.54MM")
      (fields (field (name "MFR. PART NO.") "75160-156-03LF"))
      (libsource (lib "Custom_Library") (part "Jumper 2 pin"))
    )
    (comp (ref "J26")
      (value "TH 1x2")
      (footprint "PIN HEADER 1x2 2.54mm")
      (description "CONN HEADER VERT 3POS 2.54MM")
      (fields (field (name "MFR. PART NO.") "75160-156-03LF"))
      (libsource (lib "Custom_Library") (part "Jumper 2 pin"))
    )
    (comp (ref "J27")
      (value "TH 1x2")
      (footprint "PIN HEADER 1x2 2.54mm")
      (description "CONN HEADER VERT 3POS 2.54MM")
      (fields (field (name "MFR. PART NO.") "75160-156-03LF"))
      (libsource (lib "Custom_Library") (part "Jumper 2 pin"))
    )
    (comp (ref "J28")
      (value "TH 1x2")
      (footprint "PIN HEADER 1x2 2.54mm")
      (description "CONN HEADER VERT 3POS 2.54MM")
      (fields (field (name "MFR. PART NO.") "75160-156-03LF"))
      (libsource (lib "Custom_Library") (part "Jumper 2 pin"))
    )
    (comp (ref "J29")
      (value "TH 1x2")
      (footprint "PIN HEADER 1x2 2.54mm")
      (description "CONN HEADER VERT 3POS 2.54MM")
      (fields (field (name "MFR. PART NO.") "75160-156-03LF"))
      (libsource (lib "Custom_Library") (part "Jumper 2 pin"))
    )
    (comp (ref "Q1")
      (value "DMP2120U-7")
      (footprint "SOT-23-3")
      (libsource (lib "Custom_Library") (part "MOSFET-P"))
    )
    (comp (ref "Q2")
      (value "MMBT3904")
      (footprint "SOT-23-3")
      (fields (field (name "MANUFACTURER") "Diodes Inc."))
      (libsource (lib "ESP32 Solar Charger") (part "MMBT3904"))
    )
    (comp (ref "Q3")
      (value "DMP2120U-7")
      (footprint "SOT-23-3")
      (libsource (lib "Custom_Library") (part "MOSFET-P"))
    )
    (comp (ref "Q4")
      (value "MMBT3904")
      (footprint "SOT-23-3")
      (fields (field (name "MANUFACTURER") "Diodes Inc."))
      (libsource (lib "ESP32 Solar Charger") (part "MMBT3904"))
    )
    (comp (ref "Q5")
      (value "DMP2120U-7")
      (footprint "SOT-23-3")
      (libsource (lib "Custom_Library") (part "MOSFET-P"))
    )
    (comp (ref "Q6")
      (value "MMBT3904")
      (footprint "SOT-23-3")
      (fields (field (name "MANUFACTURER") "Diodes Inc."))
      (libsource (lib "ESP32 Solar Charger") (part "MMBT3904"))
    )
    (comp (ref "Q7")
      (value "DMP2120U-7")
      (footprint "SOT-23-3")
      (libsource (lib "Custom_Library") (part "MOSFET-P"))
    )
    (comp (ref "Q8")
      (value "MMBT3904")
      (footprint "SOT-23-3")
      (fields (field (name "MANUFACTURER") "Diodes Inc."))
      (libsource (lib "ESP32 Solar Charger") (part "MMBT3904"))
    )
    (comp (ref "Q9")
      (value "DMP2120U-7")
      (footprint "SOT-23-3")
      (libsource (lib "Custom_Library") (part "MOSFET-P"))
    )
    (comp (ref "Q10")
      (value "MMBT3904")
      (footprint "SOT-23-3")
      (fields (field (name "MANUFACTURER") "Diodes Inc."))
      (libsource (lib "ESP32 Solar Charger") (part "MMBT3904"))
    )
    (comp (ref "R14")
      (value "680")
      (footprint "R-0402/1005")
      (description "Resistor")
      (fields (field (name "PUBLISHER") "Altium Limited"))
      (libsource (lib "Miscellaneous Devices") (part "Res1"))
    )
    (comp (ref "R24")
      (value "680")
      (footprint "R-0402/1005")
      (description "Resistor")
      (fields (field (name "PUBLISHER") "Altium Limited"))
      (libsource (lib "Miscellaneous Devices") (part "Res1"))
    )
    (comp (ref "R25")
      (value "680")
      (footprint "R-0402/1005")
      (description "Resistor")
      (fields (field (name "PUBLISHER") "Altium Limited"))
      (libsource (lib "Miscellaneous Devices") (part "Res1"))
    )
    (comp (ref "R26")
      (value "680")
      (footprint "R-0402/1005")
      (description "Resistor")
      (fields (field (name "PUBLISHER") "Altium Limited"))
      (libsource (lib "Miscellaneous Devices") (part "Res1"))
    )
    (comp (ref "R27")
      (value "680")
      (footprint "R-0402/1005")
      (description "Resistor")
      (fields (field (name "PUBLISHER") "Altium Limited"))
      (libsource (lib "Miscellaneous Devices") (part "Res1"))
    )
    (comp (ref "R43")
      (value "47k")
      (footprint "R-0402/1005")
      (description "Resistor")
      (fields (field (name "PUBLISHER") "Altium Limited"))
      (libsource (lib "Miscellaneous Devices") (part "Res1"))
    )
    (comp (ref "R44")
      (value "10k")
      (footprint "R-0402/1005")
      (description "Resistor")
      (fields (field (name "PUBLISHER") "Altium Limited"))
      (libsource (lib "Miscellaneous Devices") (part "Res1"))
    )
    (comp (ref "R53")
      (value "330R")
      (footprint "R-0402/1005")
      (description "Resistor")
      (fields (field (name "PUBLISHER") "Altium Limited"))
      (libsource (lib "Miscellaneous Devices") (part "Res1"))
    )
    (comp (ref "R54")
      (value "330R")
      (footprint "R-0402/1005")
      (description "Resistor")
      (fields (field (name "PUBLISHER") "Altium Limited"))
      (libsource (lib "Miscellaneous Devices") (part "Res1"))
    )
    (comp (ref "R56")
      (value "330R")
      (footprint "R-0402/1005")
      (description "Resistor")
      (fields (field (name "PUBLISHER") "Altium Limited"))
      (libsource (lib "Miscellaneous Devices") (part "Res1"))
    )
    (comp (ref "R59")
      (value "47k")
      (footprint "R-0402/1005")
      (description "Resistor")
      (fields (field (name "PUBLISHER") "Altium Limited"))
      (libsource (lib "Miscellaneous Devices") (part "Res1"))
    )
    (comp (ref "R60")
      (value "10k")
      (footprint "R-0402/1005")
      (description "Resistor")
      (fields (field (name "PUBLISHER") "Altium Limited"))
      (libsource (lib "Miscellaneous Devices") (part "Res1"))
    )
    (comp (ref "R61")
      (value "47k")
      (footprint "R-0402/1005")
      (description "Resistor")
      (fields (field (name "PUBLISHER") "Altium Limited"))
      (libsource (lib "Miscellaneous Devices") (part "Res1"))
    )
    (comp (ref "R62")
      (value "10k")
      (footprint "R-0402/1005")
      (description "Resistor")
      (fields (field (name "PUBLISHER") "Altium Limited"))
      (libsource (lib "Miscellaneous Devices") (part "Res1"))
    )
    (comp (ref "R63")
      (value "47k")
      (footprint "R-0402/1005")
      (description "Resistor")
      (fields (field (name "PUBLISHER") "Altium Limited"))
      (libsource (lib "Miscellaneous Devices") (part "Res1"))
    )
    (comp (ref "R64")
      (value "10k")
      (footprint "R-0402/1005")
      (description "Resistor")
      (fields (field (name "PUBLISHER") "Altium Limited"))
      (libsource (lib "Miscellaneous Devices") (part "Res1"))
    )
    (comp (ref "R65")
      (value "47k")
      (footprint "R-0402/1005")
      (description "Resistor")
      (fields (field (name "PUBLISHER") "Altium Limited"))
      (libsource (lib "Miscellaneous Devices") (part "Res1"))
    )
    (comp (ref "R66")
      (value "10k")
      (footprint "R-0402/1005")
      (description "Resistor")
      (fields (field (name "PUBLISHER") "Altium Limited"))
      (libsource (lib "Miscellaneous Devices") (part "Res1"))
    )
    (comp (ref "R67")
      (value "330R")
      (footprint "R-0402/1005")
      (description "Resistor")
      (fields (field (name "PUBLISHER") "Altium Limited"))
      (libsource (lib "Miscellaneous Devices") (part "Res1"))
    )
    (comp (ref "R70")
      (value "0R")
      (footprint "R-0603/1608")
      (description "Resistor")
      (fields (field (name "PUBLISHER") "Altium Limited"))
      (libsource (lib "Miscellaneous Devices") (part "Res1"))
    )
    (comp (ref "R71")
      (value "0R")
      (footprint "R-0603/1608")
      (description "Resistor")
      (fields (field (name "PUBLISHER") "Altium Limited"))
      (libsource (lib "Miscellaneous Devices") (part "Res1"))
    )
    (comp (ref "R72")
      (value "0R")
      (footprint "R-0603/1608")
      (description "Resistor")
      (fields (field (name "PUBLISHER") "Altium Limited"))
      (libsource (lib "Miscellaneous Devices") (part "Res1"))
    )
    (comp (ref "R73")
      (value "0R")
      (footprint "R-0603/1608")
      (description "Resistor")
      (fields (field (name "PUBLISHER") "Altium Limited"))
      (libsource (lib "Miscellaneous Devices") (part "Res1"))
    )
    (comp (ref "R74")
      (value "0R")
      (footprint "R-0603/1608")
      (description "Resistor")
      (fields (field (name "PUBLISHER") "Altium Limited"))
      (libsource (lib "Miscellaneous Devices") (part "Res1"))
    )
    (comp (ref "R75")
      (value "330R")
      (footprint "R-0402/1005")
      (description "Resistor")
      (fields (field (name "PUBLISHER") "Altium Limited"))
      (libsource (lib "Miscellaneous Devices") (part "Res1"))
    )
    (comp (ref "U6")
      (value "GL3224")
      (footprint "GL3224")
      (description "MEMORY CARD READER CONTROLLER")
      (fields (field (name "MANUFACTURER") "Genesys Logic Inc"))
      (libsource (lib "10X SD CARD READER") (part "GL3224"))
    )
    (comp (ref "U7")
      (value "GL3224")
      (footprint "GL3224")
      (description "MEMORY CARD READER CONTROLLER")
      (fields (field (name "MANUFACTURER") "Genesys Logic Inc"))
      (libsource (lib "10X SD CARD READER") (part "GL3224"))
    )
    (comp (ref "U8")
      (value "GL3224")
      (footprint "GL3224")
      (description "MEMORY CARD READER CONTROLLER")
      (fields (field (name "MANUFACTURER") "Genesys Logic Inc"))
      (libsource (lib "10X SD CARD READER") (part "GL3224"))
    )
    (comp (ref "U9")
      (value "GL3224")
      (footprint "GL3224")
      (description "MEMORY CARD READER CONTROLLER")
      (fields (field (name "MANUFACTURER") "Genesys Logic Inc"))
      (libsource (lib "10X SD CARD READER") (part "GL3224"))
    )
    (comp (ref "U10")
      (value "GL3224")
      (footprint "GL3224")
      (description "MEMORY CARD READER CONTROLLER")
      (fields (field (name "MANUFACTURER") "Genesys Logic Inc"))
      (libsource (lib "10X SD CARD READER") (part "GL3224"))
    )
    (comp (ref "Y4")
      (value "ECS-250-10-37B2-CKM-TR")
      (footprint "ECS-250-10-37B2")
      (libsource (lib "10X SD CARD READER SCH LIB") (part "ECS-250-10-37B2-CKM-TR"))
    )
    (comp (ref "Y5")
      (value "ECS-250-10-37B2-CKM-TR")
      (footprint "ECS-250-10-37B2")
      (libsource (lib "10X SD CARD READER SCH LIB") (part "ECS-250-10-37B2-CKM-TR"))
    )
    (comp (ref "Y6")
      (value "ECS-250-10-37B2-CKM-TR")
      (footprint "ECS-250-10-37B2")
      (libsource (lib "10X SD CARD READER SCH LIB") (part "ECS-250-10-37B2-CKM-TR"))
    )
    (comp (ref "Y7")
      (value "ECS-250-10-37B2-CKM-TR")
      (footprint "ECS-250-10-37B2")
      (libsource (lib "10X SD CARD READER SCH LIB") (part "ECS-250-10-37B2-CKM-TR"))
    )
    (comp (ref "Y8")
      (value "ECS-250-10-37B2-CKM-TR")
      (footprint "ECS-250-10-37B2")
      (libsource (lib "10X SD CARD READER SCH LIB") (part "ECS-250-10-37B2-CKM-TR"))
    )
  )
  (nets
    (net (code "1") (name "+1.2V") (class "Default")
      (node (ref "J24") (pin "1") (pinfunction "1_1") (pintype "passive"))
      (node (ref "J25") (pin "1") (pinfunction "1_1") (pintype "passive"))
      (node (ref "J26") (pin "1") (pinfunction "1_1") (pintype "passive"))
      (node (ref "J27") (pin "1") (pinfunction "1_1") (pintype "passive"))
      (node (ref "J29") (pin "1") (pinfunction "1_1") (pintype "passive"))
    )
    (net (code "2") (name "+3.3V") (class "Default")
      (node (ref "J20") (pin "1") (pinfunction "1_1") (pintype "passive"))
      (node (ref "J21") (pin "1") (pinfunction "1_1") (pintype "passive"))
      (node (ref "J22") (pin "1") (pinfunction "1_1") (pintype "passive"))
      (node (ref "J23") (pin "1") (pinfunction "1_1") (pintype "passive"))
      (node (ref "J28") (pin "1") (pinfunction "1_1") (pintype "passive"))
    )
    (net (code "4") (name "/LED1") (class "Default")
      (node (ref "R53") (pin "2") (pinfunction "2_2") (pintype "passive"))
      (node (ref "U8") (pin "21") (pinfunction "LED_21") (pintype "passive"))
    )
    (net (code "5") (name "/LED2") (class "Default")
      (node (ref "R54") (pin "2") (pinfunction "2_2") (pintype "passive"))
      (node (ref "U6") (pin "21") (pinfunction "LED_21") (pintype "passive"))
    )
    (net (code "6") (name "/LED3") (class "Default")
      (node (ref "R75") (pin "2") (pinfunction "2_2") (pintype "passive"))
      (node (ref "U10") (pin "21") (pinfunction "LED_21") (pintype "passive"))
    )
    (net (code "7") (name "/LED4") (class "Default")
      (node (ref "R56") (pin "2") (pinfunction "2_2") (pintype "passive"))
      (node (ref "U9") (pin "21") (pinfunction "LED_21") (pintype "passive"))
    )
    (net (code "8") (name "/LED5") (class "Default")
      (node (ref "R67") (pin "2") (pinfunction "2_2") (pintype "passive"))
      (node (ref "U7") (pin "21") (pinfunction "LED_21") (pintype "passive"))
    )
    (net (code "9") (name "/SD1_CD") (class "Default")
      (node (ref "J7") (pin "CD") (pinfunction "CD_CD") (pintype "passive"))
      (node (ref "U10") (pin "1") (pinfunction "SD1_CDZ_1") (pintype "passive"))
    )
    (net (code "10") (name "/SD1_CLK") (class "Default")
      (node (ref "J7") (pin "5") (pinfunction "CLK_5") (pintype "passive"))
      (node (ref "U10") (pin "39") (pinfunction "S1CKM1D0_39") (pintype "passive"))
    )
    (net (code "11") (name "/SD1_CMD") (class "Default")
      (node (ref "J7") (pin "2") (pinfunction "CMD_2") (pintype "passive"))
      (node (ref "U10") (pin "40") (pinfunction "S1CM_M1D2_40") (pintype "passive"))
    )
    (net (code "12") (name "/SD1_D0") (class "Default")
      (node (ref "J7") (pin "7") (pinfunction "DAT0_7") (pintype "passive"))
      (node (ref "U10") (pin "38") (pinfunction "S1D0_M1D1_38") (pintype "passive"))
    )
    (net (code "13") (name "/SD1_D1") (class "Default")
      (node (ref "J7") (pin "8") (pinfunction "DAT1_8") (pintype "passive"))
      (node (ref "U10") (pin "37") (pinfunction "S1D1_M1BS_37") (pintype "passive"))
    )
    (net (code "14") (name "/SD1_D2") (class "Default")
      (node (ref "J7") (pin "9") (pinfunction "DAT2_9") (pintype "passive"))
      (node (ref "U10") (pin "42") (pinfunction "S1D2_M1CK_42") (pintype "passive"))
    )
    (net (code "15") (name "/SD1_D3") (class "Default")
      (node (ref "J7") (pin "1") (pinfunction "DAT3/CD_1") (pintype "passive"))
      (node (ref "U10") (pin "41") (pinfunction "S1D3_M1D3_41") (pintype "passive"))
    )
    (net (code "16") (name "/SD1_VCC") (class "Default")
      (node (ref "C106") (pin "2") (pinfunction "2_2") (pintype "passive"))
      (node (ref "C146") (pin "2") (pinfunction "2_2") (pintype "passive"))
      (node (ref "C149") (pin "2") (pinfunction "2_2") (pintype "passive"))
      (node (ref "J7") (pin "4") (pinfunction "VDD_4") (pintype "passive"))
      (node (ref "U10") (pin "23") (pinfunction "S1M1_VCC_23") (pintype "passive"))
    )
    (net (code "17") (name "/SD2_CD") (class "Default")
      (node (ref "J12") (pin "CD") (pinfunction "CD_CD") (pintype "passive"))
      (node (ref "U10") (pin "36") (pinfunction "SD2_CDZ_36") (pintype "passive"))
    )
    (net (code "18") (name "/SD2_CLK") (class "Default")
      (node (ref "J12") (pin "5") (pinfunction "CLK_5") (pintype "passive"))
      (node (ref "U10") (pin "29") (pinfunction "S2CK_M2D0_29") (pintype "passive"))
    )
    (net (code "19") (name "/SD2_CMD") (class "Default")
      (node (ref "J12") (pin "2") (pinfunction "CMD_2") (pintype "passive"))
      (node (ref "U10") (pin "30") (pinfunction "S2CM_M2D2_30") (pintype "passive"))
    )
    (net (code "20") (name "/SD2_D0") (class "Default")
      (node (ref "J12") (pin "7") (pinfunction "DAT0_7") (pintype "passive"))
      (node (ref "U10") (pin "28") (pinfunction "S2D0_M2D1_28") (pintype "passive"))
    )
    (net (code "21") (name "/SD2_D1") (class "Default")
      (node (ref "J12") (pin "8") (pinfunction "DAT1_8") (pintype "passive"))
      (node (ref "U10") (pin "27") (pinfunction "S2D1_M2BS_27") (pintype "passive"))
    )
    (net (code "22") (name "/SD2_D2") (class "Default")
      (node (ref "J12") (pin "9") (pinfunction "DAT2_9") (pintype "passive"))
      (node (ref "U10") (pin "32") (pinfunction "S2D2_M2CK_32") (pintype "passive"))
    )
    (net (code "23") (name "/SD2_D3") (class "Default")
      (node (ref "J12") (pin "1") (pinfunction "DAT3/CD_1") (pintype "passive"))
      (node (ref "U10") (pin "31") (pinfunction "S2D3_M2D3_31") (pintype "passive"))
    )
    (net (code "24") (name "/SD2_VCC") (class "Default")
      (node (ref "C152") (pin "2") (pinfunction "2_2") (pintype "passive"))
      (node (ref "C155") (pin "2") (pinfunction "2_2") (pintype "passive"))
      (node (ref "C47") (pin "2") (pinfunction "2_2") (pintype "passive"))
      (node (ref "J12") (pin "4") (pinfunction "VDD_4") (pintype "passive"))
      (node (ref "U10") (pin "24") (pinfunction "S2M2_VCC_24") (pintype "passive"))
    )
    (net (code "25") (name "/SD3_CD") (class "Default")
      (node (ref "J8") (pin "CD") (pinfunction "CD_CD") (pintype "passive"))
      (node (ref "U6") (pin "1") (pinfunction "SD1_CDZ_1") (pintype "passive"))
    )
    (net (code "26") (name "/SD3_CLK") (class "Default")
      (node (ref "J8") (pin "5") (pinfunction "CLK_5") (pintype "passive"))
      (node (ref "U6") (pin "39") (pinfunction "S1CKM1D0_39") (pintype "passive"))
    )
    (net (code "27") (name "/SD3_CMD") (class "Default")
      (node (ref "J8") (pin "2") (pinfunction "CMD_2") (pintype "passive"))
      (node (ref "U6") (pin "40") (pinfunction "S1CM_M1D2_40") (pintype "passive"))
    )
    (net (code "28") (name "/SD3_D0") (class "Default")
      (node (ref "J8") (pin "7") (pinfunction "DAT0_7") (pintype "passive"))
      (node (ref "U6") (pin "38") (pinfunction "S1D0_M1D1_38") (pintype "passive"))
    )
    (net (code "29") (name "/SD3_D1") (class "Default")
      (node (ref "J8") (pin "8") (pinfunction "DAT1_8") (pintype "passive"))
      (node (ref "U6") (pin "37") (pinfunction "S1D1_M1BS_37") (pintype "passive"))
    )
    (net (code "30") (name "/SD3_D2") (class "Default")
      (node (ref "J8") (pin "9") (pinfunction "DAT2_9") (pintype "passive"))
      (node (ref "U6") (pin "42") (pinfunction "S1D2_M1CK_42") (pintype "passive"))
    )
    (net (code "31") (name "/SD3_D3") (class "Default")
      (node (ref "J8") (pin "1") (pinfunction "DAT3/CD_1") (pintype "passive"))
      (node (ref "U6") (pin "41") (pinfunction "S1D3_M1D3_41") (pintype "passive"))
    )
    (net (code "32") (name "/SD3_VCC") (class "Default")
      (node (ref "C154") (pin "2") (pinfunction "2_2") (pintype "passive"))
      (node (ref "C157") (pin "2") (pinfunction "2_2") (pintype "passive"))
      (node (ref "C43") (pin "2") (pinfunction "2_2") (pintype "passive"))
      (node (ref "J8") (pin "4") (pinfunction "VDD_4") (pintype "passive"))
      (node (ref "U6") (pin "23") (pinfunction "S1M1_VCC_23") (pintype "passive"))
    )
    (net (code "33") (name "/SD4_CD") (class "Default")
      (node (ref "J13") (pin "CD") (pinfunction "CD_CD") (pintype "passive"))
      (node (ref "U6") (pin "36") (pinfunction "SD2_CDZ_36") (pintype "passive"))
    )
    (net (code "34") (name "/SD4_CLK") (class "Default")
      (node (ref "J13") (pin "5") (pinfunction "CLK_5") (pintype "passive"))
      (node (ref "U6") (pin "29") (pinfunction "S2CK_M2D0_29") (pintype "passive"))
    )
    (net (code "35") (name "/SD4_CMD") (class "Default")
      (node (ref "J13") (pin "2") (pinfunction "CMD_2") (pintype "passive"))
      (node (ref "U6") (pin "30") (pinfunction "S2CM_M2D2_30") (pintype "passive"))
    )
    (net (code "36") (name "/SD4_D0") (class "Default")
      (node (ref "J13") (pin "7") (pinfunction "DAT0_7") (pintype "passive"))
      (node (ref "U6") (pin "28") (pinfunction "S2D0_M2D1_28") (pintype "passive"))
    )
    (net (code "37") (name "/SD4_D1") (class "Default")
      (node (ref "J13") (pin "8") (pinfunction "DAT1_8") (pintype "passive"))
      (node (ref "U6") (pin "27") (pinfunction "S2D1_M2BS_27") (pintype "passive"))
    )
    (net (code "38") (name "/SD4_D2") (class "Default")
      (node (ref "J13") (pin "9") (pinfunction "DAT2_9") (pintype "passive"))
      (node (ref "U6") (pin "32") (pinfunction "S2D2_M2CK_32") (pintype "passive"))
    )
    (net (code "39") (name "/SD4_D3") (class "Default")
      (node (ref "J13") (pin "1") (pinfunction "DAT3/CD_1") (pintype "passive"))
      (node (ref "U6") (pin "31") (pinfunction "S2D3_M2D3_31") (pintype "passive"))
    )
    (net (code "40") (name "/SD4_VCC") (class "Default")
      (node (ref "C148") (pin "2") (pinfunction "2_2") (pintype "passive"))
      (node (ref "C151") (pin "2") (pinfunction "2_2") (pintype "passive"))
      (node (ref "C58") (pin "2") (pinfunction "2_2") (pintype "passive"))
      (node (ref "J13") (pin "4") (pinfunction "VDD_4") (pintype "passive"))
      (node (ref "U6") (pin "24") (pinfunction "S2M2_VCC_24") (pintype "passive"))
    )
    (net (code "41") (name "/SD5_CD") (class "Default")
      (node (ref "J9") (pin "CD") (pinfunction "CD_CD") (pintype "passive"))
      (node (ref "U8") (pin "1") (pinfunction "SD1_CDZ_1") (pintype "passive"))
    )
    (net (code "42") (name "/SD5_CLK") (class "Default")
      (node (ref "J9") (pin "5") (pinfunction "CLK_5") (pintype "passive"))
      (node (ref "U8") (pin "39") (pinfunction "S1CKM1D0_39") (pintype "passive"))
    )
    (net (code "43") (name "/SD5_CMD") (class "Default")
      (node (ref "J9") (pin "2") (pinfunction "CMD_2") (pintype "passive"))
      (node (ref "U8") (pin "40") (pinfunction "S1CM_M1D2_40") (pintype "passive"))
    )
    (net (code "44") (name "/SD5_D0") (class "Default")
      (node (ref "J9") (pin "7") (pinfunction "DAT0_7") (pintype "passive"))
      (node (ref "U8") (pin "38") (pinfunction "S1D0_M1D1_38") (pintype "passive"))
    )
    (net (code "45") (name "/SD5_D1") (class "Default")
      (node (ref "J9") (pin "8") (pinfunction "DAT1_8") (pintype "passive"))
      (node (ref "U8") (pin "37") (pinfunction "S1D1_M1BS_37") (pintype "passive"))
    )
    (net (code "46") (name "/SD5_D2") (class "Default")
      (node (ref "J9") (pin "9") (pinfunction "DAT2_9") (pintype "passive"))
      (node (ref "U8") (pin "42") (pinfunction "S1D2_M1CK_42") (pintype "passive"))
    )
    (net (code "47") (name "/SD5_D3") (class "Default")
      (node (ref "J9") (pin "1") (pinfunction "DAT3/CD_1") (pintype "passive"))
      (node (ref "U8") (pin "41") (pinfunction "S1D3_M1D3_41") (pintype "passive"))
    )
    (net (code "48") (name "/SD5_VCC") (class "Default")
      (node (ref "C144") (pin "2") (pinfunction "2_2") (pintype "passive"))
      (node (ref "C145") (pin "2") (pinfunction "2_2") (pintype "passive"))
      (node (ref "C44") (pin "2") (pinfunction "2_2") (pintype "passive"))
      (node (ref "J9") (pin "4") (pinfunction "VDD_4") (pintype "passive"))
      (node (ref "U8") (pin "23") (pinfunction "S1M1_VCC_23") (pintype "passive"))
    )
    (net (code "49") (name "/SD6_CD") (class "Default")
      (node (ref "J14") (pin "CD") (pinfunction "CD_CD") (pintype "passive"))
      (node (ref "U8") (pin "36") (pinfunction "SD2_CDZ_36") (pintype "passive"))
    )
    (net (code "50") (name "/SD6_CLK") (class "Default")
      (node (ref "J14") (pin "5") (pinfunction "CLK_5") (pintype "passive"))
      (node (ref "U8") (pin "29") (pinfunction "S2CK_M2D0_29") (pintype "passive"))
    )
    (net (code "51") (name "/SD6_CMD") (class "Default")
      (node (ref "J14") (pin "2") (pinfunction "CMD_2") (pintype "passive"))
      (node (ref "U8") (pin "30") (pinfunction "S2CM_M2D2_30") (pintype "passive"))
    )
    (net (code "52") (name "/SD6_D0") (class "Default")
      (node (ref "J14") (pin "7") (pinfunction "DAT0_7") (pintype "passive"))
      (node (ref "U8") (pin "28") (pinfunction "S2D0_M2D1_28") (pintype "passive"))
    )
    (net (code "53") (name "/SD6_D1") (class "Default")
      (node (ref "J14") (pin "8") (pinfunction "DAT1_8") (pintype "passive"))
      (node (ref "U8") (pin "27") (pinfunction "S2D1_M2BS_27") (pintype "passive"))
    )
    (net (code "54") (name "/SD6_D2") (class "Default")
      (node (ref "J14") (pin "9") (pinfunction "DAT2_9") (pintype "passive"))
      (node (ref "U8") (pin "32") (pinfunction "S2D2_M2CK_32") (pintype "passive"))
    )
    (net (code "55") (name "/SD6_D3") (class "Default")
      (node (ref "J14") (pin "1") (pinfunction "DAT3/CD_1") (pintype "passive"))
      (node (ref "U8") (pin "31") (pinfunction "S2D3_M2D3_31") (pintype "passive"))
    )
    (net (code "56") (name "/SD6_VCC") (class "Default")
      (node (ref "C142") (pin "2") (pinfunction "2_2") (pintype "passive"))
      (node (ref "C143") (pin "2") (pinfunction "2_2") (pintype "passive"))
      (node (ref "C59") (pin "2") (pinfunction "2_2") (pintype "passive"))
      (node (ref "J14") (pin "4") (pinfunction "VDD_4") (pintype "passive"))
      (node (ref "U8") (pin "24") (pinfunction "S2M2_VCC_24") (pintype "passive"))
    )
    (net (code "57") (name "/SD7_CD") (class "Default")
      (node (ref "J10") (pin "CD") (pinfunction "CD_CD") (pintype "passive"))
      (node (ref "U7") (pin "1") (pinfunction "SD1_CDZ_1") (pintype "passive"))
    )
    (net (code "58") (name "/SD7_CLK") (class "Default")
      (node (ref "J10") (pin "5") (pinfunction "CLK_5") (pintype "passive"))
      (node (ref "U7") (pin "39") (pinfunction "S1CKM1D0_39") (pintype "passive"))
    )
    (net (code "59") (name "/SD7_CMD") (class "Default")
      (node (ref "J10") (pin "2") (pinfunction "CMD_2") (pintype "passive"))
      (node (ref "U7") (pin "40") (pinfunction "S1CM_M1D2_40") (pintype "passive"))
    )
    (net (code "60") (name "/SD7_D0") (class "Default")
      (node (ref "J10") (pin "7") (pinfunction "DAT0_7") (pintype "passive"))
      (node (ref "U7") (pin "38") (pinfunction "S1D0_M1D1_38") (pintype "passive"))
    )
    (net (code "61") (name "/SD7_D1") (class "Default")
      (node (ref "J10") (pin "8") (pinfunction "DAT1_8") (pintype "passive"))
      (node (ref "U7") (pin "37") (pinfunction "S1D1_M1BS_37") (pintype "passive"))
    )
    (net (code "62") (name "/SD7_D2") (class "Default")
      (node (ref "J10") (pin "9") (pinfunction "DAT2_9") (pintype "passive"))
      (node (ref "U7") (pin "42") (pinfunction "S1D2_M1CK_42") (pintype "passive"))
    )
    (net (code "63") (name "/SD7_D3") (class "Default")
      (node (ref "J10") (pin "1") (pinfunction "DAT3/CD_1") (pintype "passive"))
      (node (ref "U7") (pin "41") (pinfunction "S1D3_M1D3_41") (pintype "passive"))
    )
    (net (code "64") (name "/SD7_VCC") (class "Default")
      (node (ref "C160") (pin "2") (pinfunction "2_2") (pintype "passive"))
      (node (ref "C161") (pin "2") (pinfunction "2_2") (pintype "passive"))
      (node (ref "C45") (pin "2") (pinfunction "2_2") (pintype "passive"))
      (node (ref "J10") (pin "4") (pinfunction "VDD_4") (pintype "passive"))
      (node (ref "U7") (pin "23") (pinfunction "S1M1_VCC_23") (pintype "passive"))
    )
    (net (code "65") (name "/SD8_CD") (class "Default")
      (node (ref "J15") (pin "CD") (pinfunction "CD_CD") (pintype "passive"))
      (node (ref "U7") (pin "36") (pinfunction "SD2_CDZ_36") (pintype "passive"))
    )
    (net (code "66") (name "/SD8_CLK") (class "Default")
      (node (ref "J15") (pin "5") (pinfunction "CLK_5") (pintype "passive"))
      (node (ref "U7") (pin "29") (pinfunction "S2CK_M2D0_29") (pintype "passive"))
    )
    (net (code "67") (name "/SD8_CMD") (class "Default")
      (node (ref "J15") (pin "2") (pinfunction "CMD_2") (pintype "passive"))
      (node (ref "U7") (pin "30") (pinfunction "S2CM_M2D2_30") (pintype "passive"))
    )
    (net (code "68") (name "/SD8_D0") (class "Default")
      (node (ref "J15") (pin "7") (pinfunction "DAT0_7") (pintype "passive"))
      (node (ref "U7") (pin "28") (pinfunction "S2D0_M2D1_28") (pintype "passive"))
    )
    (net (code "69") (name "/SD8_D1") (class "Default")
      (node (ref "J15") (pin "8") (pinfunction "DAT1_8") (pintype "passive"))
      (node (ref "U7") (pin "27") (pinfunction "S2D1_M2BS_27") (pintype "passive"))
    )
    (net (code "70") (name "/SD8_D2") (class "Default")
      (node (ref "J15") (pin "9") (pinfunction "DAT2_9") (pintype "passive"))
      (node (ref "U7") (pin "32") (pinfunction "S2D2_M2CK_32") (pintype "passive"))
    )
    (net (code "71") (name "/SD8_D3") (class "Default")
      (node (ref "J15") (pin "1") (pinfunction "DAT3/CD_1") (pintype "passive"))
      (node (ref "U7") (pin "31") (pinfunction "S2D3_M2D3_31") (pintype "passive"))
    )
    (net (code "72") (name "/SD8_VCC") (class "Default")
      (node (ref "C158") (pin "2") (pinfunction "2_2") (pintype "passive"))
      (node (ref "C159") (pin "2") (pinfunction "2_2") (pintype "passive"))
      (node (ref "C60") (pin "2") (pinfunction "2_2") (pintype "passive"))
      (node (ref "J15") (pin "4") (pinfunction "VDD_4") (pintype "passive"))
      (node (ref "U7") (pin "24") (pinfunction "S2M2_VCC_24") (pintype "passive"))
    )
    (net (code "73") (name "/SD9_CD") (class "Default")
      (node (ref "J11") (pin "CD") (pinfunction "CD_CD") (pintype "passive"))
      (node (ref "U9") (pin "1") (pinfunction "SD1_CDZ_1") (pintype "passive"))
    )
    (net (code "74") (name "/SD9_CLK") (class "Default")
      (node (ref "J11") (pin "5") (pinfunction "CLK_5") (pintype "passive"))
      (node (ref "U9") (pin "39") (pinfunction "S1CKM1D0_39") (pintype "passive"))
    )
    (net (code "75") (name "/SD9_CMD") (class "Default")
      (node (ref "J11") (pin "2") (pinfunction "CMD_2") (pintype "passive"))
      (node (ref "U9") (pin "40") (pinfunction "S1CM_M1D2_40") (pintype "passive"))
    )
    (net (code "76") (name "/SD9_D0") (class "Default")
      (node (ref "J11") (pin "7") (pinfunction "DAT0_7") (pintype "passive"))
      (node (ref "U9") (pin "38") (pinfunction "S1D0_M1D1_38") (pintype "passive"))
    )
    (net (code "77") (name "/SD9_D1") (class "Default")
      (node (ref "J11") (pin "8") (pinfunction "DAT1_8") (pintype "passive"))
      (node (ref "U9") (pin "37") (pinfunction "S1D1_M1BS_37") (pintype "passive"))
    )
    (net (code "78") (name "/SD9_D2") (class "Default")
      (node (ref "J11") (pin "9") (pinfunction "DAT2_9") (pintype "passive"))
      (node (ref "U9") (pin "42") (pinfunction "S1D2_M1CK_42") (pintype "passive"))
    )
    (net (code "79") (name "/SD9_D3") (class "Default")
      (node (ref "J11") (pin "1") (pinfunction "DAT3/CD_1") (pintype "passive"))
      (node (ref "U9") (pin "41") (pinfunction "S1D3_M1D3_41") (pintype "passive"))
    )
    (net (code "80") (name "/SD9_VCC") (class "Default")
      (node (ref "C147") (pin "2") (pinfunction "2_2") (pintype "passive"))
      (node (ref "C150") (pin "2") (pinfunction "2_2") (pintype "passive"))
      (node (ref "C46") (pin "2") (pinfunction "2_2") (pintype "passive"))
      (node (ref "J11") (pin "4") (pinfunction "VDD_4") (pintype "passive"))
      (node (ref "U9") (pin "23") (pinfunction "S1M1_VCC_23") (pintype "passive"))
    )
    (net (code "81") (name "/SD10_CD") (class "Default")
      (node (ref "J16") (pin "CD") (pinfunction "CD_CD") (pintype "passive"))
      (node (ref "U9") (pin "36") (pinfunction "SD2_CDZ_36") (pintype "passive"))
    )
    (net (code "82") (name "/SD10_CLK") (class "Default")
      (node (ref "J16") (pin "5") (pinfunction "CLK_5") (pintype "passive"))
      (node (ref "U9") (pin "29") (pinfunction "S2CK_M2D0_29") (pintype "passive"))
    )
    (net (code "83") (name "/SD10_CMD") (class "Default")
      (node (ref "J16") (pin "2") (pinfunction "CMD_2") (pintype "passive"))
      (node (ref "U9") (pin "30") (pinfunction "S2CM_M2D2_30") (pintype "passive"))
    )
    (net (code "84") (name "/SD10_D0") (class "Default")
      (node (ref "J16") (pin "7") (pinfunction "DAT0_7") (pintype "passive"))
      (node (ref "U9") (pin "28") (pinfunction "S2D0_M2D1_28") (pintype "passive"))
    )
    (net (code "85") (name "/SD10_D1") (class "Default")
      (node (ref "J16") (pin "8") (pinfunction "DAT1_8") (pintype "passive"))
      (node (ref "U9") (pin "27") (pinfunction "S2D1_M2BS_27") (pintype "passive"))
    )
    (net (code "86") (name "/SD10_D2") (class "Default")
      (node (ref "J16") (pin "9") (pinfunction "DAT2_9") (pintype "passive"))
      (node (ref "U9") (pin "32") (pinfunction "S2D2_M2CK_32") (pintype "passive"))
    )
    (net (code "87") (name "/SD10_D3") (class "Default")
      (node (ref "J16") (pin "1") (pinfunction "DAT3/CD_1") (pintype "passive"))
      (node (ref "U9") (pin "31") (pinfunction "S2D3_M2D3_31") (pintype "passive"))
    )
    (net (code "88") (name "/SD10_VCC") (class "Default")
      (node (ref "C153") (pin "2") (pinfunction "2_2") (pintype "passive"))
      (node (ref "C156") (pin "2") (pinfunction "2_2") (pintype "passive"))
      (node (ref "C61") (pin "2") (pinfunction "2_2") (pintype "passive"))
      (node (ref "J16") (pin "4") (pinfunction "VDD_4") (pintype "passive"))
      (node (ref "U9") (pin "24") (pinfunction "S2M2_VCC_24") (pintype "passive"))
    )
    (net (code "89") (name "/XTAL1_IN") (class "Default")
      (node (ref "C102") (pin "1") (pinfunction "1_1") (pintype "passive"))
      (node (ref "U10") (pin "13") (pinfunction "X1_13") (pintype "passive"))
      (node (ref "Y5") (pin "1") (pinfunction "1_1") (pintype "passive"))
    )
    (net (code "90") (name "/XTAL1_OUT") (class "Default")
      (node (ref "C104") (pin "1") (pinfunction "1_1") (pintype "passive"))
      (node (ref "U10") (pin "14") (pinfunction "X2_14") (pintype "passive"))
      (node (ref "Y5") (pin "3") (pinfunction "2_3") (pintype "passive"))
    )
    (net (code "91") (name "/XTAL2_IN") (class "Default")
      (node (ref "C49") (pin "1") (pinfunction "1_1") (pintype "passive"))
      (node (ref "U6") (pin "13") (pinfunction "X1_13") (pintype "passive"))
      (node (ref "Y4") (pin "1") (pinfunction "1_1") (pintype "passive"))
    )
    (net (code "92") (name "/XTAL2_OUT") (class "Default")
      (node (ref "C48") (pin "1") (pinfunction "1_1") (pintype "passive"))
      (node (ref "U6") (pin "14") (pinfunction "X2_14") (pintype "passive"))
      (node (ref "Y4") (pin "3") (pinfunction "2_3") (pintype "passive"))
    )
    (net (code "93") (name "/XTAL3_IN") (class "Default")
      (node (ref "C103") (pin "1") (pinfunction "1_1") (pintype "passive"))
      (node (ref "U8") (pin "13") (pinfunction "X1_13") (pintype "passive"))
      (node (ref "Y6") (pin "1") (pinfunction "1_1") (pintype "passive"))
    )
    (net (code "94") (name "/XTAL3_OUT") (class "Default")
      (node (ref "C105") (pin "1") (pinfunction "1_1") (pintype "passive"))
      (node (ref "U8") (pin "14") (pinfunction "X2_14") (pintype "passive"))
      (node (ref "Y6") (pin "3") (pinfunction "2_3") (pintype "passive"))
    )
    (net (code "95") (name "/XTAL4_IN") (class "Default")
      (node (ref "C137") (pin "1") (pinfunction "1_1") (pintype "passive"))
      (node (ref "U9") (pin "13") (pinfunction "X1_13") (pintype "passive"))
      (node (ref "Y8") (pin "1") (pinfunction "1_1") (pintype "passive"))
    )
    (net (code "96") (name "/XTAL4_OUT") (class "Default")
      (node (ref "C139") (pin "1") (pinfunction "1_1") (pintype "passive"))
      (node (ref "U9") (pin "14") (pinfunction "X2_14") (pintype "passive"))
      (node (ref "Y8") (pin "3") (pinfunction "2_3") (pintype "passive"))
    )
    (net (code "97") (name "/XTAL5_IN") (class "Default")
      (node (ref "C136") (pin "1") (pinfunction "1_1") (pintype "passive"))
      (node (ref "U7") (pin "13") (pinfunction "X1_13") (pintype "passive"))
      (node (ref "Y7") (pin "1") (pinfunction "1_1") (pintype "passive"))
    )
    (net (code "98") (name "/XTAL5_OUT") (class "Default")
      (node (ref "C138") (pin "1") (pinfunction "1_1") (pintype "passive"))
      (node (ref "U7") (pin "14") (pinfunction "X2_14") (pintype "passive"))
      (node (ref "Y7") (pin "3") (pinfunction "2_3") (pintype "passive"))
    )
    (net (code "99") (name "GND") (class "Default")
      (node (ref "C100") (pin "1") (pinfunction "1_1") (pintype "passive"))
      (node (ref "C102") (pin "2") (pinfunction "2_2") (pintype "passive"))
      (node (ref "C103") (pin "2") (pinfunction "2_2") (pintype "passive"))
      (node (ref "C104") (pin "2") (pinfunction "2_2") (pintype "passive"))
      (node (ref "C105") (pin "2") (pinfunction "2_2") (pintype "passive"))
      (node (ref "C106") (pin "1") (pinfunction "1_1") (pintype "passive"))
      (node (ref "C108") (pin "1") (pinfunction "1_1") (pintype "passive"))
      (node (ref "C109") (pin "1") (pinfunction "1_1") (pintype "passive"))
      (node (ref "C110") (pin "1") (pinfunction "1_1") (pintype "passive"))
      (node (ref "C111") (pin "1") (pinfunction "1_1") (pintype "passive"))
      (node (ref "C112") (pin "1") (pinfunction "1_1") (pintype "passive"))
      (node (ref "C113") (pin "1") (pinfunction "1_1") (pintype "passive"))
      (node (ref "C114") (pin "1") (pinfunction "1_1") (pintype "passive"))
      (node (ref "C115") (pin "1") (pinfunction "1_1") (pintype "passive"))
      (node (ref "C116") (pin "1") (pinfunction "1_1") (pintype "passive"))
      (node (ref "C117") (pin "1") (pinfunction "1_1") (pintype "passive"))
      (node (ref "C118") (pin "1") (pinfunction "1_1") (pintype "passive"))
      (node (ref "C119") (pin "1") (pinfunction "1_1") (pintype "passive"))
      (node (ref "C120") (pin "1") (pinfunction "1_1") (pintype "passive"))
      (node (ref "C121") (pin "1") (pinfunction "1_1") (pintype "passive"))
      (node (ref "C122") (pin "1") (pinfunction "1_1") (pintype "passive"))
      (node (ref "C123") (pin "1") (pinfunction "1_1") (pintype "passive"))
      (node (ref "C124") (pin "1") (pinfunction "1_1") (pintype "passive"))
      (node (ref "C125") (pin "1") (pinfunction "1_1") (pintype "passive"))
      (node (ref "C126") (pin "1") (pinfunction "1_1") (pintype "passive"))
      (node (ref "C127") (pin "1") (pinfunction "1_1") (pintype "passive"))
      (node (ref "C128") (pin "1") (pinfunction "1_1") (pintype "passive"))
      (node (ref "C129") (pin "1") (pinfunction "1_1") (pintype "passive"))
      (node (ref "C130") (pin "1") (pinfunction "1_1") (pintype "passive"))
      (node (ref "C131") (pin "1") (pinfunction "1_1") (pintype "passive"))
      (node (ref "C132") (pin "1") (pinfunction "1_1") (pintype "passive"))
      (node (ref "C133") (pin "1") (pinfunction "1_1") (pintype "passive"))
      (node (ref "C134") (pin "1") (pinfunction "1_1") (pintype "passive"))
      (node (ref "C135") (pin "1") (pinfunction "1_1") (pintype "passive"))
      (node (ref "C136") (pin "2") (pinfunction "2_2") (pintype "passive"))
      (node (ref "C137") (pin "2") (pinfunction "2_2") (pintype "passive"))
      (node (ref "C138") (pin "2") (pinfunction "2_2") (pintype "passive"))
      (node (ref "C139") (pin "2") (pinfunction "2_2") (pintype "passive"))
      (node (ref "C140") (pin "1") (pinfunction "1_1") (pintype "passive"))
      (node (ref "C141") (pin "1") (pinfunction "1_1") (pintype "passive"))
      (node (ref "C142") (pin "1") (pinfunction "1_1") (pintype "passive"))
      (node (ref "C143") (pin "1") (pinfunction "1_1") (pintype "passive"))
      (node (ref "C144") (pin "1") (pinfunction "1_1") (pintype "passive"))
      (node (ref "C145") (pin "1") (pinfunction "1_1") (pintype "passive"))
      (node (ref "C146") (pin "1") (pinfunction "1_1") (pintype "passive"))
      (node (ref "C147") (pin "1") (pinfunction "1_1") (pintype "passive"))
      (node (ref "C148") (pin "1") (pinfunction "1_1") (pintype "passive"))
      (node (ref "C149") (pin "1") (pinfunction "1_1") (pintype "passive"))
      (node (ref "C150") (pin "1") (pinfunction "1_1") (pintype "passive"))
      (node (ref "C151") (pin "1") (pinfunction "1_1") (pintype "passive"))
      (node (ref "C152") (pin "1") (pinfunction "1_1") (pintype "passive"))
      (node (ref "C153") (pin "1") (pinfunction "1_1") (pintype "passive"))
      (node (ref "C154") (pin "1") (pinfunction "1_1") (pintype "passive"))
      (node (ref "C155") (pin "1") (pinfunction "1_1") (pintype "passive"))
      (node (ref "C156") (pin "1") (pinfunction "1_1") (pintype "passive"))
      (node (ref "C157") (pin "1") (pinfunction "1_1") (pintype "passive"))
      (node (ref "C158") (pin "1") (pinfunction "1_1") (pintype "passive"))
      (node (ref "C159") (pin "1") (pinfunction "1_1") (pintype "passive"))
      (node (ref "C160") (pin "1") (pinfunction "1_1") (pintype "passive"))
      (node (ref "C161") (pin "1") (pinfunction "1_1") (pintype "passive"))
      (node (ref "C43") (pin "1") (pinfunction "1_1") (pintype "passive"))
      (node (ref "C44") (pin "1") (pinfunction "1_1") (pintype "passive"))
      (node (ref "C45") (pin "1") (pinfunction "1_1") (pintype "passive"))
      (node (ref "C46") (pin "1") (pinfunction "1_1") (pintype "passive"))
      (node (ref "C47") (pin "1") (pinfunction "1_1") (pintype "passive"))
      (node (ref "C48") (pin "2") (pinfunction "2_2") (pintype "passive"))
      (node (ref "C49") (pin "2") (pinfunction "2_2") (pintype "passive"))
      (node (ref "C54") (pin "1") (pinfunction "1_1") (pintype "passive"))
      (node (ref "C55") (pin "1") (pinfunction "1_1") (pintype "passive"))
      (node (ref "C56") (pin "1") (pinfunction "1_1") (pintype "passive"))
      (node (ref "C57") (pin "1") (pinfunction "1_1") (pintype "passive"))
      (node (ref "C58") (pin "1") (pinfunction "1_1") (pintype "passive"))
      (node (ref "C59") (pin "1") (pinfunction "1_1") (pintype "passive"))
      (node (ref "C60") (pin "1") (pinfunction "1_1") (pintype "passive"))
      (node (ref "C61") (pin "1") (pinfunction "1_1") (pintype "passive"))
      (node (ref "C70") (pin "1") (pinfunction "1_1") (pintype "passive"))
      (node (ref "C71") (pin "1") (pinfunction "1_1") (pintype "passive"))
      (node (ref "C72") (pin "1") (pinfunction "1_1") (pintype "passive"))
      (node (ref "C73") (pin "1") (pinfunction "1_1") (pintype "passive"))
      (node (ref "C74") (pin "1") (pinfunction "1_1") (pintype "passive"))
      (node (ref "C75") (pin "1") (pinfunction "1_1") (pintype "passive"))
      (node (ref "C76") (pin "1") (pinfunction "1_1") (pintype "passive"))
      (node (ref "C77") (pin "1") (pinfunction "1_1") (pintype "passive"))
      (node (ref "C78") (pin "1") (pinfunction "1_1") (pintype "passive"))
      (node (ref "C79") (pin "1") (pinfunction "1_1") (pintype "passive"))
      (node (ref "C80") (pin "1") (pinfunction "1_1") (pintype "passive"))
      (node (ref "C81") (pin "1") (pinfunction "1_1") (pintype "passive"))
      (node (ref "C82") (pin "1") (pinfunction "1_1") (pintype "passive"))
      (node (ref "C83") (pin "1") (pinfunction "1_1") (pintype "passive"))
      (node (ref "C84") (pin "1") (pinfunction "1_1") (pintype "passive"))
      (node (ref "C85") (pin "1") (pinfunction "1_1") (pintype "passive"))
      (node (ref "C86") (pin "1") (pinfunction "1_1") (pintype "passive"))
      (node (ref "C87") (pin "1") (pinfunction "1_1") (pintype "passive"))
      (node (ref "C88") (pin "1") (pinfunction "1_1") (pintype "passive"))
      (node (ref "C89") (pin "1") (pinfunction "1_1") (pintype "passive"))
      (node (ref "C90") (pin "1") (pinfunction "1_1") (pintype "passive"))
      (node (ref "C92") (pin "1") (pinfunction "1_1") (pintype "passive"))
      (node (ref "C94") (pin "1") (pinfunction "1_1") (pintype "passive"))
      (node (ref "C96") (pin "1") (pinfunction "1_1") (pintype "passive"))
      (node (ref "C98") (pin "1") (pinfunction "1_1") (pintype "passive"))
      (node (ref "D4") (pin "C") (pinfunction "C_C") (pintype "passive"))
      (node (ref "D5") (pin "C") (pinfunction "C_C") (pintype "passive"))
      (node (ref "D6") (pin "C") (pinfunction "C_C") (pintype "passive"))
      (node (ref "D7") (pin "C") (pinfunction "C_C") (pintype "passive"))
      (node (ref "D8") (pin "C") (pinfunction "C_C") (pintype "passive"))
      (node (ref "J10") (pin "3") (pinfunction "VSS_3") (pintype "passive"))
      (node (ref "J10") (pin "6") (pinfunction "VSS_6") (pintype "passive"))
      (node (ref "J10") (pin "G1") (pinfunction "GND_G1") (pintype "passive"))
      (node (ref "J10") (pin "G2") (pinfunction "GND_G2") (pintype "passive"))
      (node (ref "J11") (pin "3") (pinfunction "VSS_3") (pintype "passive"))
      (node (ref "J11") (pin "6") (pinfunction "VSS_6") (pintype "passive"))
      (node (ref "J11") (pin "G1") (pinfunction "GND_G1") (pintype "passive"))
      (node (ref "J11") (pin "G2") (pinfunction "GND_G2") (pintype "passive"))
      (node (ref "J12") (pin "3") (pinfunction "VSS_3") (pintype "passive"))
      (node (ref "J12") (pin "6") (pinfunction "VSS_6") (pintype "passive"))
      (node (ref "J12") (pin "G1") (pinfunction "GND_G1") (pintype "passive"))
      (node (ref "J12") (pin "G2") (pinfunction "GND_G2") (pintype "passive"))
      (node (ref "J13") (pin "3") (pinfunction "VSS_3") (pintype "passive"))
      (node (ref "J13") (pin "6") (pinfunction "VSS_6") (pintype "passive"))
      (node (ref "J13") (pin "G1") (pinfunction "GND_G1") (pintype "passive"))
      (node (ref "J13") (pin "G2") (pinfunction "GND_G2") (pintype "passive"))
      (node (ref "J14") (pin "3") (pinfunction "VSS_3") (pintype "passive"))
      (node (ref "J14") (pin "6") (pinfunction "VSS_6") (pintype "passive"))
      (node (ref "J14") (pin "G1") (pinfunction "GND_G1") (pintype "passive"))
      (node (ref "J14") (pin "G2") (pinfunction "GND_G2") (pintype "passive"))
      (node (ref "J15") (pin "3") (pinfunction "VSS_3") (pintype "passive"))
      (node (ref "J15") (pin "6") (pinfunction "VSS_6") (pintype "passive"))
      (node (ref "J15") (pin "G1") (pinfunction "GND_G1") (pintype "passive"))
      (node (ref "J15") (pin "G2") (pinfunction "GND_G2") (pintype "passive"))
      (node (ref "J16") (pin "3") (pinfunction "VSS_3") (pintype "passive"))
      (node (ref "J16") (pin "6") (pinfunction "VSS_6") (pintype "passive"))
      (node (ref "J16") (pin "G1") (pinfunction "GND_G1") (pintype "passive"))
      (node (ref "J16") (pin "G2") (pinfunction "GND_G2") (pintype "passive"))
      (node (ref "J7") (pin "3") (pinfunction "VSS_3") (pintype "passive"))
      (node (ref "J7") (pin "6") (pinfunction "VSS_6") (pintype "passive"))
      (node (ref "J7") (pin "G1") (pinfunction "GND_G1") (pintype "passive"))
      (node (ref "J7") (pin "G2") (pinfunction "GND_G2") (pintype "passive"))
      (node (ref "J8") (pin "3") (pinfunction "VSS_3") (pintype "passive"))
      (node (ref "J8") (pin "6") (pinfunction "VSS_6") (pintype "passive"))
      (node (ref "J8") (pin "G1") (pinfunction "GND_G1") (pintype "passive"))
      (node (ref "J8") (pin "G2") (pinfunction "GND_G2") (pintype "passive"))
      (node (ref "J9") (pin "3") (pinfunction "VSS_3") (pintype "passive"))
      (node (ref "J9") (pin "6") (pinfunction "VSS_6") (pintype "passive"))
      (node (ref "J9") (pin "G1") (pinfunction "GND_G1") (pintype "passive"))
      (node (ref "J9") (pin "G2") (pinfunction "GND_G2") (pintype "passive"))
      (node (ref "Q10") (pin "2") (pinfunction "E_2") (pintype "passive"))
      (node (ref "Q2") (pin "2") (pinfunction "E_2") (pintype "passive"))
      (node (ref "Q4") (pin "2") (pinfunction "E_2") (pintype "passive"))
      (node (ref "Q6") (pin "2") (pinfunction "E_2") (pintype "passive"))
      (node (ref "Q8") (pin "2") (pinfunction "E_2") (pintype "passive"))
      (node (ref "R14") (pin "1") (pinfunction "1_1") (pintype "passive"))
      (node (ref "R24") (pin "1") (pinfunction "1_1") (pintype "passive"))
      (node (ref "R25") (pin "1") (pinfunction "1_1") (pintype "passive"))
      (node (ref "R26") (pin "1") (pinfunction "1_1") (pintype "passive"))
      (node (ref "R27") (pin "1") (pinfunction "1_1") (pintype "passive"))
      (node (ref "U10") (pin "12") (pinfunction "GND_12") (pintype "passive"))
      (node (ref "U10") (pin "3") (pinfunction "GND_3") (pintype "passive"))
      (node (ref "U10") (pin "49") (pinfunction "EPAD_49") (pintype "passive"))
      (node (ref "U6") (pin "12") (pinfunction "GND_12") (pintype "passive"))
      (node (ref "U6") (pin "3") (pinfunction "GND_3") (pintype "passive"))
      (node (ref "U6") (pin "49") (pinfunction "EPAD_49") (pintype "passive"))
      (node (ref "U7") (pin "12") (pinfunction "GND_12") (pintype "passive"))
      (node (ref "U7") (pin "3") (pinfunction "GND_3") (pintype "passive"))
      (node (ref "U7") (pin "49") (pinfunction "EPAD_49") (pintype "passive"))
      (node (ref "U8") (pin "12") (pinfunction "GND_12") (pintype "passive"))
      (node (ref "U8") (pin "3") (pinfunction "GND_3") (pintype "passive"))
      (node (ref "U8") (pin "49") (pinfunction "EPAD_49") (pintype "passive"))
      (node (ref "U9") (pin "12") (pinfunction "GND_12") (pintype "passive"))
      (node (ref "U9") (pin "3") (pinfunction "GND_3") (pintype "passive"))
      (node (ref "U9") (pin "49") (pinfunction "EPAD_49") (pintype "passive"))
      (node (ref "Y4") (pin "2") (pinfunction "GND_2") (pintype "power_in"))
      (node (ref "Y4") (pin "4") (pinfunction "GND_4") (pintype "power_in"))
      (node (ref "Y5") (pin "2") (pinfunction "GND_2") (pintype "power_in"))
      (node (ref "Y5") (pin "4") (pinfunction "GND_4") (pintype "power_in"))
      (node (ref "Y6") (pin "2") (pinfunction "GND_2") (pintype "power_in"))
      (node (ref "Y6") (pin "4") (pinfunction "GND_4") (pintype "power_in"))
      (node (ref "Y7") (pin "2") (pinfunction "GND_2") (pintype "power_in"))
      (node (ref "Y7") (pin "4") (pinfunction "GND_4") (pintype "power_in"))
      (node (ref "Y8") (pin "2") (pinfunction "GND_2") (pintype "power_in"))
      (node (ref "Y8") (pin "4") (pinfunction "GND_4") (pintype "power_in"))
    )
    (net (code "100") (name "Net-(C54-Pad2)") (class "Default")
      (node (ref "C54") (pin "2") (pinfunction "2_2") (pintype "passive"))
      (node (ref "C55") (pin "2") (pinfunction "2_2") (pintype "passive"))
      (node (ref "C56") (pin "2") (pinfunction "2_2") (pintype "passive"))
      (node (ref "C57") (pin "2") (pinfunction "2_2") (pintype "passive"))
      (node (ref "J20") (pin "2") (pinfunction "2_2") (pintype "passive"))
      (node (ref "U8") (pin "15") (pinfunction "AVDD33_15") (pintype "passive"))
      (node (ref "U8") (pin "25") (pinfunction "DVDD33_25") (pintype "passive"))
      (node (ref "U8") (pin "34") (pinfunction "DVDD33_34") (pintype "passive"))
      (node (ref "U8") (pin "44") (pinfunction "DVDD33_44") (pintype "passive"))
      (node (ref "U8") (pin "6") (pinfunction "AVDD33_6") (pintype "passive"))
    )
    (net (code "101") (name "Net-(C70-Pad2)") (class "Default")
      (node (ref "C70") (pin "2") (pinfunction "2_2") (pintype "passive"))
      (node (ref "C71") (pin "2") (pinfunction "2_2") (pintype "passive"))
      (node (ref "C72") (pin "2") (pinfunction "2_2") (pintype "passive"))
      (node (ref "C73") (pin "2") (pinfunction "2_2") (pintype "passive"))
      (node (ref "J21") (pin "2") (pinfunction "2_2") (pintype "passive"))
      (node (ref "U6") (pin "15") (pinfunction "AVDD33_15") (pintype "passive"))
      (node (ref "U6") (pin "25") (pinfunction "DVDD33_25") (pintype "passive"))
      (node (ref "U6") (pin "34") (pinfunction "DVDD33_34") (pintype "passive"))
      (node (ref "U6") (pin "44") (pinfunction "DVDD33_44") (pintype "passive"))
      (node (ref "U6") (pin "6") (pinfunction "AVDD33_6") (pintype "passive"))
    )
    (net (code "102") (name "Net-(C74-Pad2)") (class "Default")
      (node (ref "C74") (pin "2") (pinfunction "2_2") (pintype "passive"))
      (node (ref "C75") (pin "2") (pinfunction "2_2") (pintype "passive"))
      (node (ref "C76") (pin "2") (pinfunction "2_2") (pintype "passive"))
      (node (ref "C77") (pin "2") (pinfunction "2_2") (pintype "passive"))
      (node (ref "J22") (pin "2") (pinfunction "2_2") (pintype "passive"))
      (node (ref "U10") (pin "15") (pinfunction "AVDD33_15") (pintype "passive"))
      (node (ref "U10") (pin "25") (pinfunction "DVDD33_25") (pintype "passive"))
      (node (ref "U10") (pin "34") (pinfunction "DVDD33_34") (pintype "passive"))
      (node (ref "U10") (pin "44") (pinfunction "DVDD33_44") (pintype "passive"))
      (node (ref "U10") (pin "6") (pinfunction "AVDD33_6") (pintype "passive"))
    )
    (net (code "103") (name "Net-(C108-Pad2)") (class "Default")
      (node (ref "C108") (pin "2") (pinfunction "2_2") (pintype "passive"))
      (node (ref "C109") (pin "2") (pinfunction "2_2") (pintype "passive"))
      (node (ref "C110") (pin "2") (pinfunction "2_2") (pintype "passive"))
      (node (ref "C111") (pin "2") (pinfunction "2_2") (pintype "passive"))
      (node (ref "J23") (pin "2") (pinfunction "2_2") (pintype "passive"))
      (node (ref "U9") (pin "15") (pinfunction "AVDD33_15") (pintype "passive"))
      (node (ref "U9") (pin "25") (pinfunction "DVDD33_25") (pintype "passive"))
      (node (ref "U9") (pin "34") (pinfunction "DVDD33_34") (pintype "passive"))
      (node (ref "U9") (pin "44") (pinfunction "DVDD33_44") (pintype "passive"))
      (node (ref "U9") (pin "6") (pinfunction "AVDD33_6") (pintype "passive"))
    )
    (net (code "104") (name "Net-(C112-Pad2)") (class "Default")
      (node (ref "C112") (pin "2") (pinfunction "2_2") (pintype "passive"))
      (node (ref "C113") (pin "2") (pinfunction "2_2") (pintype "passive"))
      (node (ref "C114") (pin "2") (pinfunction "2_2") (pintype "passive"))
      (node (ref "C115") (pin "2") (pinfunction "2_2") (pintype "passive"))
      (node (ref "J28") (pin "2") (pinfunction "2_2") (pintype "passive"))
      (node (ref "U7") (pin "15") (pinfunction "AVDD33_15") (pintype "passive"))
      (node (ref "U7") (pin "25") (pinfunction "DVDD33_25") (pintype "passive"))
      (node (ref "U7") (pin "34") (pinfunction "DVDD33_34") (pintype "passive"))
      (node (ref "U7") (pin "44") (pinfunction "DVDD33_44") (pintype "passive"))
      (node (ref "U7") (pin "6") (pinfunction "AVDD33_6") (pintype "passive"))
    )
    (net (code "105") (name "Net-(D4-PadA)") (class "Default")
      (node (ref "D4") (pin "A") (pinfunction "A_A") (pintype "passive"))
      (node (ref "R53") (pin "1") (pinfunction "1_1") (pintype "passive"))
    )
    (net (code "106") (name "Net-(D5-PadA)") (class "Default")
      (node (ref "D5") (pin "A") (pinfunction "A_A") (pintype "passive"))
      (node (ref "R54") (pin "1") (pinfunction "1_1") (pintype "passive"))
    )
    (net (code "107") (name "Net-(D6-PadA)") (class "Default")
      (node (ref "D6") (pin "A") (pinfunction "A_A") (pintype "passive"))
      (node (ref "R75") (pin "1") (pinfunction "1_1") (pintype "passive"))
    )
    (net (code "108") (name "Net-(D7-PadA)") (class "Default")
      (node (ref "D7") (pin "A") (pinfunction "A_A") (pintype "passive"))
      (node (ref "R56") (pin "1") (pinfunction "1_1") (pintype "passive"))
    )
    (net (code "109") (name "Net-(D8-PadA)") (class "Default")
      (node (ref "D8") (pin "A") (pinfunction "A_A") (pintype "passive"))
      (node (ref "R67") (pin "1") (pinfunction "1_1") (pintype "passive"))
    )
    (net (code "110") (name "Net-(Q1-Pad3)") (class "Default")
      (node (ref "Q1") (pin "3") (pinfunction "3_3") (pintype "passive"))
      (node (ref "R71") (pin "1") (pinfunction "1_1") (pintype "passive"))
    )
    (net (code "111") (name "Net-(Q2-B)") (class "Default")
      (node (ref "Q2") (pin "1") (pinfunction "B_1") (pintype "passive"))
      (node (ref "R44") (pin "2") (pinfunction "2_2") (pintype "passive"))
    )
    (net (code "112") (name "Net-(Q2-C)") (class "Default")
      (node (ref "Q1") (pin "1") (pinfunction "1_1") (pintype "passive"))
      (node (ref "Q2") (pin "3") (pinfunction "C_3") (pintype "passive"))
      (node (ref "R43") (pin "2") (pinfunction "2_2") (pintype "passive"))
    )
    (net (code "113") (name "Net-(Q3-Pad3)") (class "Default")
      (node (ref "Q3") (pin "3") (pinfunction "3_3") (pintype "passive"))
      (node (ref "R72") (pin "1") (pinfunction "1_1") (pintype "passive"))
    )
    (net (code "114") (name "Net-(Q4-B)") (class "Default")
      (node (ref "Q4") (pin "1") (pinfunction "B_1") (pintype "passive"))
      (node (ref "R60") (pin "2") (pinfunction "2_2") (pintype "passive"))
    )
    (net (code "115") (name "Net-(Q4-C)") (class "Default")
      (node (ref "Q3") (pin "1") (pinfunction "1_1") (pintype "passive"))
      (node (ref "Q4") (pin "3") (pinfunction "C_3") (pintype "passive"))
      (node (ref "R59") (pin "2") (pinfunction "2_2") (pintype "passive"))
    )
    (net (code "116") (name "Net-(Q5-Pad3)") (class "Default")
      (node (ref "Q5") (pin "3") (pinfunction "3_3") (pintype "passive"))
      (node (ref "R73") (pin "1") (pinfunction "1_1") (pintype "passive"))
    )
    (net (code "117") (name "Net-(Q6-B)") (class "Default")
      (node (ref "Q6") (pin "1") (pinfunction "B_1") (pintype "passive"))
      (node (ref "R62") (pin "2") (pinfunction "2_2") (pintype "passive"))
    )
    (net (code "118") (name "Net-(Q6-C)") (class "Default")
      (node (ref "Q5") (pin "1") (pinfunction "1_1") (pintype "passive"))
      (node (ref "Q6") (pin "3") (pinfunction "C_3") (pintype "passive"))
      (node (ref "R61") (pin "2") (pinfunction "2_2") (pintype "passive"))
    )
    (net (code "119") (name "Net-(Q7-Pad3)") (class "Default")
      (node (ref "Q7") (pin "3") (pinfunction "3_3") (pintype "passive"))
      (node (ref "R70") (pin "1") (pinfunction "1_1") (pintype "passive"))
    )
    (net (code "120") (name "Net-(Q8-B)") (class "Default")
      (node (ref "Q8") (pin "1") (pinfunction "B_1") (pintype "passive"))
      (node (ref "R64") (pin "2") (pinfunction "2_2") (pintype "passive"))
    )
    (net (code "121") (name "Net-(Q8-C)") (class "Default")
      (node (ref "Q7") (pin "1") (pinfunction "1_1") (pintype "passive"))
      (node (ref "Q8") (pin "3") (pinfunction "C_3") (pintype "passive"))
      (node (ref "R63") (pin "2") (pinfunction "2_2") (pintype "passive"))
    )
    (net (code "122") (name "Net-(Q9-Pad3)") (class "Default")
      (node (ref "Q9") (pin "3") (pinfunction "3_3") (pintype "passive"))
      (node (ref "R74") (pin "1") (pinfunction "1_1") (pintype "passive"))
    )
    (net (code "123") (name "Net-(Q10-B)") (class "Default")
      (node (ref "Q10") (pin "1") (pinfunction "B_1") (pintype "passive"))
      (node (ref "R66") (pin "2") (pinfunction "2_2") (pintype "passive"))
    )
    (net (code "124") (name "Net-(Q10-C)") (class "Default")
      (node (ref "Q10") (pin "3") (pinfunction "C_3") (pintype "passive"))
      (node (ref "Q9") (pin "1") (pinfunction "1_1") (pintype "passive"))
      (node (ref "R65") (pin "2") (pinfunction "2_2") (pintype "passive"))
    )
    (net (code "125") (name "Net-(U6-AVDD12)") (class "Default")
      (node (ref "C82") (pin "2") (pinfunction "2_2") (pintype "passive"))
      (node (ref "C83") (pin "2") (pinfunction "2_2") (pintype "passive"))
      (node (ref "C84") (pin "2") (pinfunction "2_2") (pintype "passive"))
      (node (ref "C85") (pin "2") (pinfunction "2_2") (pintype "passive"))
      (node (ref "J25") (pin "2") (pinfunction "2_2") (pintype "passive"))
      (node (ref "U6") (pin "26") (pinfunction "DVDD12_26") (pintype "passive"))
      (node (ref "U6") (pin "9") (pinfunction "AVDD12_9") (pintype "passive"))
    )
    (net (code "126") (name "Net-(U6-RTERM)") (class "Default")
      (node (ref "R14") (pin "2") (pinfunction "2_2") (pintype "passive"))
      (node (ref "U6") (pin "16") (pinfunction "RTERM_16") (pintype "passive"))
    )
    (net (code "127") (name "Net-(U6-TXN)") (class "Default")
      (node (ref "C68") (pin "2") (pinfunction "2_2") (pintype "passive"))
      (node (ref "U6") (pin "7") (pinfunction "TXN_7") (pintype "passive"))
    )
    (net (code "128") (name "Net-(U6-TXP)") (class "Default")
      (node (ref "C95") (pin "2") (pinfunction "2_2") (pintype "passive"))
      (node (ref "U6") (pin "8") (pinfunction "TXP_8") (pintype "passive"))
    )
    (net (code "129") (name "Net-(U6-VBUS)") (class "Default")
      (node (ref "C94") (pin "2") (pinfunction "2_2") (pintype "passive"))
      (node (ref "C96") (pin "2") (pinfunction "2_2") (pintype "passive"))
      (node (ref "R71") (pin "2") (pinfunction "2_2") (pintype "passive"))
      (node (ref "U6") (pin "22") (pinfunction "VBUS_22") (pintype "passive"))
    )
    (net (code "130") (name "Net-(U6-VUHS_1)") (class "Default")
      (node (ref "C117") (pin "2") (pinfunction "2_2") (pintype "passive"))
      (node (ref "U6") (pin "43") (pinfunction "VUHS_1_43") (pintype "passive"))
    )
    (net (code "131") (name "Net-(U6-VUHS_2)") (class "Default")
      (node (ref "C133") (pin "2") (pinfunction "2_2") (pintype "passive"))
      (node (ref "U6") (pin "33") (pinfunction "VUHS_2_33") (pintype "passive"))
    )
    (net (code "132") (name "Net-(U7-AVDD12)") (class "Default")
      (node (ref "C122") (pin "2") (pinfunction "2_2") (pintype "passive"))
      (node (ref "C123") (pin "2") (pinfunction "2_2") (pintype "passive"))
      (node (ref "C124") (pin "2") (pinfunction "2_2") (pintype "passive"))
      (node (ref "C125") (pin "2") (pinfunction "2_2") (pintype "passive"))
      (node (ref "J29") (pin "2") (pinfunction "2_2") (pintype "passive"))
      (node (ref "U7") (pin "26") (pinfunction "DVDD12_26") (pintype "passive"))
      (node (ref "U7") (pin "9") (pinfunction "AVDD12_9") (pintype "passive"))
    )
    (net (code "133") (name "Net-(U7-RTERM)") (class "Default")
      (node (ref "R27") (pin "2") (pinfunction "2_2") (pintype "passive"))
      (node (ref "U7") (pin "16") (pinfunction "RTERM_16") (pintype "passive"))
    )
    (net (code "134") (name "Net-(U7-TXN)") (class "Default")
      (node (ref "C101") (pin "2") (pinfunction "2_2") (pintype "passive"))
      (node (ref "U7") (pin "7") (pinfunction "TXN_7") (pintype "passive"))
    )
    (net (code "135") (name "Net-(U7-TXP)") (class "Default")
      (node (ref "C107") (pin "2") (pinfunction "2_2") (pintype "passive"))
      (node (ref "U7") (pin "8") (pinfunction "TXP_8") (pintype "passive"))
    )
    (net (code "136") (name "Net-(U7-VBUS)") (class "Default")
      (node (ref "C130") (pin "2") (pinfunction "2_2") (pintype "passive"))
      (node (ref "C132") (pin "2") (pinfunction "2_2") (pintype "passive"))
      (node (ref "R74") (pin "2") (pinfunction "2_2") (pintype "passive"))
      (node (ref "U7") (pin "22") (pinfunction "VBUS_22") (pintype "passive"))
    )
    (net (code "137") (name "Net-(U7-VUHS_1)") (class "Default")
      (node (ref "C140") (pin "2") (pinfunction "2_2") (pintype "passive"))
      (node (ref "U7") (pin "43") (pinfunction "VUHS_1_43") (pintype "passive"))
    )
    (net (code "138") (name "Net-(U7-VUHS_2)") (class "Default")
      (node (ref "C141") (pin "2") (pinfunction "2_2") (pintype "passive"))
      (node (ref "U7") (pin "33") (pinfunction "VUHS_2_33") (pintype "passive"))
    )
    (net (code "139") (name "Net-(U8-AVDD12)") (class "Default")
      (node (ref "C78") (pin "2") (pinfunction "2_2") (pintype "passive"))
      (node (ref "C79") (pin "2") (pinfunction "2_2") (pintype "passive"))
      (node (ref "C80") (pin "2") (pinfunction "2_2") (pintype "passive"))
      (node (ref "C81") (pin "2") (pinfunction "2_2") (pintype "passive"))
      (node (ref "J24") (pin "2") (pinfunction "2_2") (pintype "passive"))
      (node (ref "U8") (pin "26") (pinfunction "DVDD12_26") (pintype "passive"))
      (node (ref "U8") (pin "9") (pinfunction "AVDD12_9") (pintype "passive"))
    )
    (net (code "140") (name "Net-(U8-RTERM)") (class "Default")
      (node (ref "R24") (pin "2") (pinfunction "2_2") (pintype "passive"))
      (node (ref "U8") (pin "16") (pinfunction "RTERM_16") (pintype "passive"))
    )
    (net (code "141") (name "Net-(U8-TXN)") (class "Default")
      (node (ref "C35") (pin "2") (pinfunction "2_2") (pintype "passive"))
      (node (ref "U8") (pin "7") (pinfunction "TXN_7") (pintype "passive"))
    )
    (net (code "142") (name "Net-(U8-TXP)") (class "Default")
      (node (ref "C93") (pin "2") (pinfunction "2_2") (pintype "passive"))
      (node (ref "U8") (pin "8") (pinfunction "TXP_8") (pintype "passive"))
    )
    (net (code "143") (name "Net-(U8-VBUS)") (class "Default")
      (node (ref "C90") (pin "2") (pinfunction "2_2") (pintype "passive"))
      (node (ref "C92") (pin "2") (pinfunction "2_2") (pintype "passive"))
      (node (ref "R70") (pin "2") (pinfunction "2_2") (pintype "passive"))
      (node (ref "U8") (pin "22") (pinfunction "VBUS_22") (pintype "passive"))
    )
    (net (code "144") (name "Net-(U8-VUHS_1)") (class "Default")
      (node (ref "C116") (pin "2") (pinfunction "2_2") (pintype "passive"))
      (node (ref "U8") (pin "43") (pinfunction "VUHS_1_43") (pintype "passive"))
    )
    (net (code "145") (name "Net-(U8-VUHS_2)") (class "Default")
      (node (ref "C131") (pin "2") (pinfunction "2_2") (pintype "passive"))
      (node (ref "U8") (pin "33") (pinfunction "VUHS_2_33") (pintype "passive"))
    )
    (net (code "146") (name "Net-(U9-AVDD12)") (class "Default")
      (node (ref "C118") (pin "2") (pinfunction "2_2") (pintype "passive"))
      (node (ref "C119") (pin "2") (pinfunction "2_2") (pintype "passive"))
      (node (ref "C120") (pin "2") (pinfunction "2_2") (pintype "passive"))
      (node (ref "C121") (pin "2") (pinfunction "2_2") (pintype "passive"))
      (node (ref "J27") (pin "2") (pinfunction "2_2") (pintype "passive"))
      (node (ref "U9") (pin "26") (pinfunction "DVDD12_26") (pintype "passive"))
      (node (ref "U9") (pin "9") (pinfunction "AVDD12_9") (pintype "passive"))
    )
    (net (code "147") (name "Net-(U9-RTERM)") (class "Default")
      (node (ref "R26") (pin "2") (pinfunction "2_2") (pintype "passive"))
      (node (ref "U9") (pin "16") (pinfunction "RTERM_16") (pintype "passive"))
    )
    (net (code "148") (name "Net-(U9-TXN)") (class "Default")
      (node (ref "C91") (pin "2") (pinfunction "2_2") (pintype "passive"))
      (node (ref "U9") (pin "7") (pinfunction "TXN_7") (pintype "passive"))
    )
    (net (code "149") (name "Net-(U9-TXP)") (class "Default")
      (node (ref "C99") (pin "2") (pinfunction "2_2") (pintype "passive"))
      (node (ref "U9") (pin "8") (pinfunction "TXP_8") (pintype "passive"))
    )
    (net (code "150") (name "Net-(U9-VBUS)") (class "Default")
      (node (ref "C126") (pin "2") (pinfunction "2_2") (pintype "passive"))
      (node (ref "C128") (pin "2") (pinfunction "2_2") (pintype "passive"))
      (node (ref "R73") (pin "2") (pinfunction "2_2") (pintype "passive"))
      (node (ref "U9") (pin "22") (pinfunction "VBUS_22") (pintype "passive"))
    )
    (net (code "151") (name "Net-(U9-VUHS_1)") (class "Default")
      (node (ref "C129") (pin "2") (pinfunction "2_2") (pintype "passive"))
      (node (ref "U9") (pin "43") (pinfunction "VUHS_1_43") (pintype "passive"))
    )
    (net (code "152") (name "Net-(U9-VUHS_2)") (class "Default")
      (node (ref "C135") (pin "2") (pinfunction "2_2") (pintype "passive"))
      (node (ref "U9") (pin "33") (pinfunction "VUHS_2_33") (pintype "passive"))
    )
    (net (code "153") (name "Net-(U10-AVDD12)") (class "Default")
      (node (ref "C86") (pin "2") (pinfunction "2_2") (pintype "passive"))
      (node (ref "C87") (pin "2") (pinfunction "2_2") (pintype "passive"))
      (node (ref "C88") (pin "2") (pinfunction "2_2") (pintype "passive"))
      (node (ref "C89") (pin "2") (pinfunction "2_2") (pintype "passive"))
      (node (ref "J26") (pin "2") (pinfunction "2_2") (pintype "passive"))
      (node (ref "U10") (pin "26") (pinfunction "DVDD12_26") (pintype "passive"))
      (node (ref "U10") (pin "9") (pinfunction "AVDD12_9") (pintype "passive"))
    )
    (net (code "154") (name "Net-(U10-RTERM)") (class "Default")
      (node (ref "R25") (pin "2") (pinfunction "2_2") (pintype "passive"))
      (node (ref "U10") (pin "16") (pinfunction "RTERM_16") (pintype "passive"))
    )
    (net (code "155") (name "Net-(U10-TXN)") (class "Default")
      (node (ref "C69") (pin "2") (pinfunction "2_2") (pintype "passive"))
      (node (ref "U10") (pin "7") (pinfunction "TXN_7") (pintype "passive"))
    )
    (net (code "156") (name "Net-(U10-TXP)") (class "Default")
      (node (ref "C97") (pin "2") (pinfunction "2_2") (pintype "passive"))
      (node (ref "U10") (pin "8") (pinfunction "TXP_8") (pintype "passive"))
    )
    (net (code "157") (name "Net-(U10-VBUS)") (class "Default")
      (node (ref "C100") (pin "2") (pinfunction "2_2") (pintype "passive"))
      (node (ref "C98") (pin "2") (pinfunction "2_2") (pintype "passive"))
      (node (ref "R72") (pin "2") (pinfunction "2_2") (pintype "passive"))
      (node (ref "U10") (pin "22") (pinfunction "VBUS_22") (pintype "passive"))
    )
    (net (code "158") (name "Net-(U10-VUHS_1)") (class "Default")
      (node (ref "C127") (pin "2") (pinfunction "2_2") (pintype "passive"))
      (node (ref "U10") (pin "43") (pinfunction "VUHS_1_43") (pintype "passive"))
    )
    (net (code "159") (name "Net-(U10-VUHS_2)") (class "Default")
      (node (ref "C134") (pin "2") (pinfunction "2_2") (pintype "passive"))
      (node (ref "U10") (pin "33") (pinfunction "VUHS_2_33") (pintype "passive"))
    )
    (net (code "160") (name "SD_EN_1,2") (class "Default")
      (node (ref "R60") (pin "1") (pinfunction "1_1") (pintype "passive"))
    )
    (net (code "161") (name "SD_EN_3,4") (class "Default")
      (node (ref "R44") (pin "1") (pinfunction "1_1") (pintype "passive"))
    )
    (net (code "162") (name "SD_EN_5,6") (class "Default")
      (node (ref "R64") (pin "1") (pinfunction "1_1") (pintype "passive"))
    )
    (net (code "163") (name "SD_EN_7,8") (class "Default")
      (node (ref "R66") (pin "1") (pinfunction "1_1") (pintype "passive"))
    )
    (net (code "164") (name "SD_EN_9,10") (class "Default")
      (node (ref "R62") (pin "1") (pinfunction "1_1") (pintype "passive"))
    )
    (net (code "165") (name "USB2.0_DN_PORT1_N") (class "Default")
      (node (ref "U10") (pin "4") (pinfunction "DM_4") (pintype "passive"))
    )
    (net (code "166") (name "USB2.0_DN_PORT1_P") (class "Default")
      (node (ref "U10") (pin "5") (pinfunction "DP_5") (pintype "passive"))
    )
    (net (code "167") (name "USB2.0_DN_PORT2_N") (class "Default")
      (node (ref "U6") (pin "4") (pinfunction "DM_4") (pintype "passive"))
    )
    (net (code "168") (name "USB2.0_DN_PORT2_P") (class "Default")
      (node (ref "U6") (pin "5") (pinfunction "DP_5") (pintype "passive"))
    )
    (net (code "169") (name "USB2.0_DN_PORT3_N") (class "Default")
      (node (ref "U8") (pin "4") (pinfunction "DM_4") (pintype "passive"))
    )
    (net (code "170") (name "USB2.0_DN_PORT3_P") (class "Default")
      (node (ref "U8") (pin "5") (pinfunction "DP_5") (pintype "passive"))
    )
    (net (code "171") (name "USB2.0_DN_PORT4_N") (class "Default")
      (node (ref "U7") (pin "4") (pinfunction "DM_4") (pintype "passive"))
    )
    (net (code "172") (name "USB2.0_DN_PORT4_P") (class "Default")
      (node (ref "U7") (pin "5") (pinfunction "DP_5") (pintype "passive"))
    )
    (net (code "173") (name "USB2.0_DN_PORT5_N") (class "Default")
      (node (ref "U9") (pin "4") (pinfunction "DM_4") (pintype "passive"))
    )
    (net (code "174") (name "USB2.0_DN_PORT5_P") (class "Default")
      (node (ref "U9") (pin "5") (pinfunction "DP_5") (pintype "passive"))
    )
    (net (code "175") (name "USB3.0_DN_PORT1_RX_N") (class "Default")
      (node (ref "U10") (pin "10") (pinfunction "RXN_10") (pintype "passive"))
    )
    (net (code "176") (name "USB3.0_DN_PORT1_RX_P") (class "Default")
      (node (ref "U10") (pin "11") (pinfunction "RXP_11") (pintype "passive"))
    )
    (net (code "177") (name "USB3.0_DN_PORT1_TX_N") (class "Default")
      (node (ref "C97") (pin "1") (pinfunction "1_1") (pintype "passive"))
    )
    (net (code "178") (name "USB3.0_DN_PORT1_TX_P") (class "Default")
      (node (ref "C69") (pin "1") (pinfunction "1_1") (pintype "passive"))
    )
    (net (code "179") (name "USB3.0_DN_PORT2_RX_N") (class "Default")
      (node (ref "U6") (pin "10") (pinfunction "RXN_10") (pintype "passive"))
    )
    (net (code "180") (name "USB3.0_DN_PORT2_RX_P") (class "Default")
      (node (ref "U6") (pin "11") (pinfunction "RXP_11") (pintype "passive"))
    )
    (net (code "181") (name "USB3.0_DN_PORT2_TX_N") (class "Default")
      (node (ref "C68") (pin "1") (pinfunction "1_1") (pintype "passive"))
    )
    (net (code "182") (name "USB3.0_DN_PORT2_TX_P") (class "Default")
      (node (ref "C95") (pin "1") (pinfunction "1_1") (pintype "passive"))
    )
    (net (code "183") (name "USB3.0_DN_PORT3_RX_N") (class "Default")
      (node (ref "U8") (pin "10") (pinfunction "RXN_10") (pintype "passive"))
    )
    (net (code "184") (name "USB3.0_DN_PORT3_RX_P") (class "Default")
      (node (ref "U8") (pin "11") (pinfunction "RXP_11") (pintype "passive"))
    )
    (net (code "185") (name "USB3.0_DN_PORT3_TX_N") (class "Default")
      (node (ref "C35") (pin "1") (pinfunction "1_1") (pintype "passive"))
    )
    (net (code "186") (name "USB3.0_DN_PORT3_TX_P") (class "Default")
      (node (ref "C93") (pin "1") (pinfunction "1_1") (pintype "passive"))
    )
    (net (code "187") (name "USB3.0_DN_PORT4_RX_N") (class "Default")
      (node (ref "U7") (pin "10") (pinfunction "RXN_10") (pintype "passive"))
    )
    (net (code "188") (name "USB3.0_DN_PORT4_RX_P") (class "Default")
      (node (ref "U7") (pin "11") (pinfunction "RXP_11") (pintype "passive"))
    )
    (net (code "189") (name "USB3.0_DN_PORT4_TX_N") (class "Default")
      (node (ref "C101") (pin "1") (pinfunction "1_1") (pintype "passive"))
    )
    (net (code "190") (name "USB3.0_DN_PORT4_TX_P") (class "Default")
      (node (ref "C107") (pin "1") (pinfunction "1_1") (pintype "passive"))
    )
    (net (code "191") (name "USB3.0_DN_PORT5_RX_N") (class "Default")
      (node (ref "U9") (pin "10") (pinfunction "RXN_10") (pintype "passive"))
    )
    (net (code "192") (name "USB3.0_DN_PORT5_RX_P") (class "Default")
      (node (ref "U9") (pin "11") (pinfunction "RXP_11") (pintype "passive"))
    )
    (net (code "193") (name "USB3.0_DN_PORT5_TX_N") (class "Default")
      (node (ref "C91") (pin "1") (pinfunction "1_1") (pintype "passive"))
    )
    (net (code "194") (name "USB3.0_DN_PORT5_TX_P") (class "Default")
      (node (ref "C99") (pin "1") (pinfunction "1_1") (pintype "passive"))
    )
    (net (code "195") (name "VBUS") (class "Default")
      (node (ref "Q1") (pin "2") (pinfunction "2_2") (pintype "passive"))
      (node (ref "Q3") (pin "2") (pinfunction "2_2") (pintype "passive"))
      (node (ref "Q5") (pin "2") (pinfunction "2_2") (pintype "passive"))
      (node (ref "Q7") (pin "2") (pinfunction "2_2") (pintype "passive"))
      (node (ref "Q9") (pin "2") (pinfunction "2_2") (pintype "passive"))
      (node (ref "R43") (pin "1") (pinfunction "1_1") (pintype "passive"))
      (node (ref "R59") (pin "1") (pinfunction "1_1") (pintype "passive"))
      (node (ref "R61") (pin "1") (pinfunction "1_1") (pintype "passive"))
      (node (ref "R63") (pin "1") (pinfunction "1_1") (pintype "passive"))
      (node (ref "R65") (pin "1") (pinfunction "1_1") (pintype "passive"))
    )
    (net (code "196") (name "unconnected-(J7-PadWP)") (class "Default")
      (node (ref "J7") (pin "WP") (pinfunction "WP_WP") (pintype "passive+no_connect"))
    )
    (net (code "197") (name "unconnected-(J8-PadWP)") (class "Default")
      (node (ref "J8") (pin "WP") (pinfunction "WP_WP") (pintype "passive+no_connect"))
    )
    (net (code "198") (name "unconnected-(J9-PadWP)") (class "Default")
      (node (ref "J9") (pin "WP") (pinfunction "WP_WP") (pintype "passive+no_connect"))
    )
    (net (code "199") (name "unconnected-(J10-PadWP)") (class "Default")
      (node (ref "J10") (pin "WP") (pinfunction "WP_WP") (pintype "passive+no_connect"))
    )
    (net (code "200") (name "unconnected-(J11-PadWP)") (class "Default")
      (node (ref "J11") (pin "WP") (pinfunction "WP_WP") (pintype "passive+no_connect"))
    )
    (net (code "201") (name "unconnected-(J12-PadWP)") (class "Default")
      (node (ref "J12") (pin "WP") (pinfunction "WP_WP") (pintype "passive+no_connect"))
    )
    (net (code "202") (name "unconnected-(J13-PadWP)") (class "Default")
      (node (ref "J13") (pin "WP") (pinfunction "WP_WP") (pintype "passive+no_connect"))
    )
    (net (code "203") (name "unconnected-(J14-PadWP)") (class "Default")
      (node (ref "J14") (pin "WP") (pinfunction "WP_WP") (pintype "passive+no_connect"))
    )
    (net (code "204") (name "unconnected-(J15-PadWP)") (class "Default")
      (node (ref "J15") (pin "WP") (pinfunction "WP_WP") (pintype "passive+no_connect"))
    )
    (net (code "205") (name "unconnected-(J16-PadWP)") (class "Default")
      (node (ref "J16") (pin "WP") (pinfunction "WP_WP") (pintype "passive+no_connect"))
    )
    (net (code "206") (name "unconnected-(U6-MS2_INS-Pad35)") (class "Default")
      (node (ref "U6") (pin "35") (pinfunction "MS2_INS_35") (pintype "passive+no_connect"))
    )
    (net (code "207") (name "unconnected-(U6-S1D4_M1D7-Pad48)") (class "Default")
      (node (ref "U6") (pin "48") (pinfunction "S1D4_M1D7_48") (pintype "passive+no_connect"))
    )
    (net (code "208") (name "unconnected-(U6-S1D5_M1D6-Pad47)") (class "Default")
      (node (ref "U6") (pin "47") (pinfunction "S1D5_M1D6_47") (pintype "passive+no_connect"))
    )
    (net (code "209") (name "unconnected-(U6-S1D6_M1D5-Pad46)") (class "Default")
      (node (ref "U6") (pin "46") (pinfunction "S1D6_M1D5_46") (pintype "passive+no_connect"))
    )
    (net (code "210") (name "unconnected-(U6-S1D7_M1D4-Pad45)") (class "Default")
      (node (ref "U6") (pin "45") (pinfunction "S1D7_M1D4_45") (pintype "passive+no_connect"))
    )
    (net (code "211") (name "unconnected-(U6-SD1_WP-Pad2)") (class "Default")
      (node (ref "U6") (pin "2") (pinfunction "SD1_WP_2") (pintype "passive+no_connect"))
    )
    (net (code "212") (name "unconnected-(U6-SPI_CK-Pad19)") (class "Default")
      (node (ref "U6") (pin "19") (pinfunction "SPI_CK_19") (pintype "passive+no_connect"))
    )
    (net (code "213") (name "unconnected-(U6-SPI_CS-Pad20)") (class "Default")
      (node (ref "U6") (pin "20") (pinfunction "SPI_CS_20") (pintype "passive+no_connect"))
    )
    (net (code "214") (name "unconnected-(U6-SPI_MISO-Pad17)") (class "Default")
      (node (ref "U6") (pin "17") (pinfunction "SPI_MISO_17") (pintype "passive+no_connect"))
    )
    (net (code "215") (name "unconnected-(U6-SPI_MOSI-Pad18)") (class "Default")
      (node (ref "U6") (pin "18") (pinfunction "SPI_MOSI_18") (pintype "passive+no_connect"))
    )
    (net (code "216") (name "unconnected-(U7-MS2_INS-Pad35)") (class "Default")
      (node (ref "U7") (pin "35") (pinfunction "MS2_INS_35") (pintype "passive+no_connect"))
    )
    (net (code "217") (name "unconnected-(U7-S1D4_M1D7-Pad48)") (class "Default")
      (node (ref "U7") (pin "48") (pinfunction "S1D4_M1D7_48") (pintype "passive+no_connect"))
    )
    (net (code "218") (name "unconnected-(U7-S1D5_M1D6-Pad47)") (class "Default")
      (node (ref "U7") (pin "47") (pinfunction "S1D5_M1D6_47") (pintype "passive+no_connect"))
    )
    (net (code "219") (name "unconnected-(U7-S1D6_M1D5-Pad46)") (class "Default")
      (node (ref "U7") (pin "46") (pinfunction "S1D6_M1D5_46") (pintype "passive+no_connect"))
    )
    (net (code "220") (name "unconnected-(U7-S1D7_M1D4-Pad45)") (class "Default")
      (node (ref "U7") (pin "45") (pinfunction "S1D7_M1D4_45") (pintype "passive+no_connect"))
    )
    (net (code "221") (name "unconnected-(U7-SD1_WP-Pad2)") (class "Default")
      (node (ref "U7") (pin "2") (pinfunction "SD1_WP_2") (pintype "passive+no_connect"))
    )
    (net (code "222") (name "unconnected-(U7-SPI_CK-Pad19)") (class "Default")
      (node (ref "U7") (pin "19") (pinfunction "SPI_CK_19") (pintype "passive+no_connect"))
    )
    (net (code "223") (name "unconnected-(U7-SPI_CS-Pad20)") (class "Default")
      (node (ref "U7") (pin "20") (pinfunction "SPI_CS_20") (pintype "passive+no_connect"))
    )
    (net (code "224") (name "unconnected-(U7-SPI_MISO-Pad17)") (class "Default")
      (node (ref "U7") (pin "17") (pinfunction "SPI_MISO_17") (pintype "passive+no_connect"))
    )
    (net (code "225") (name "unconnected-(U7-SPI_MOSI-Pad18)") (class "Default")
      (node (ref "U7") (pin "18") (pinfunction "SPI_MOSI_18") (pintype "passive+no_connect"))
    )
    (net (code "226") (name "unconnected-(U8-MS2_INS-Pad35)") (class "Default")
      (node (ref "U8") (pin "35") (pinfunction "MS2_INS_35") (pintype "passive+no_connect"))
    )
    (net (code "227") (name "unconnected-(U8-S1D4_M1D7-Pad48)") (class "Default")
      (node (ref "U8") (pin "48") (pinfunction "S1D4_M1D7_48") (pintype "passive+no_connect"))
    )
    (net (code "228") (name "unconnected-(U8-S1D5_M1D6-Pad47)") (class "Default")
      (node (ref "U8") (pin "47") (pinfunction "S1D5_M1D6_47") (pintype "passive+no_connect"))
    )
    (net (code "229") (name "unconnected-(U8-S1D6_M1D5-Pad46)") (class "Default")
      (node (ref "U8") (pin "46") (pinfunction "S1D6_M1D5_46") (pintype "passive+no_connect"))
    )
    (net (code "230") (name "unconnected-(U8-S1D7_M1D4-Pad45)") (class "Default")
      (node (ref "U8") (pin "45") (pinfunction "S1D7_M1D4_45") (pintype "passive+no_connect"))
    )
    (net (code "231") (name "unconnected-(U8-SD1_WP-Pad2)") (class "Default")
      (node (ref "U8") (pin "2") (pinfunction "SD1_WP_2") (pintype "passive+no_connect"))
    )
    (net (code "232") (name "unconnected-(U8-SPI_CK-Pad19)") (class "Default")
      (node (ref "U8") (pin "19") (pinfunction "SPI_CK_19") (pintype "passive+no_connect"))
    )
    (net (code "233") (name "unconnected-(U8-SPI_CS-Pad20)") (class "Default")
      (node (ref "U8") (pin "20") (pinfunction "SPI_CS_20") (pintype "passive+no_connect"))
    )
    (net (code "234") (name "unconnected-(U8-SPI_MISO-Pad17)") (class "Default")
      (node (ref "U8") (pin "17") (pinfunction "SPI_MISO_17") (pintype "passive+no_connect"))
    )
    (net (code "235") (name "unconnected-(U8-SPI_MOSI-Pad18)") (class "Default")
      (node (ref "U8") (pin "18") (pinfunction "SPI_MOSI_18") (pintype "passive+no_connect"))
    )
    (net (code "236") (name "unconnected-(U9-MS2_INS-Pad35)") (class "Default")
      (node (ref "U9") (pin "35") (pinfunction "MS2_INS_35") (pintype "passive+no_connect"))
    )
    (net (code "237") (name "unconnected-(U9-S1D4_M1D7-Pad48)") (class "Default")
      (node (ref "U9") (pin "48") (pinfunction "S1D4_M1D7_48") (pintype "passive+no_connect"))
    )
    (net (code "238") (name "unconnected-(U9-S1D5_M1D6-Pad47)") (class "Default")
      (node (ref "U9") (pin "47") (pinfunction "S1D5_M1D6_47") (pintype "passive+no_connect"))
    )
    (net (code "239") (name "unconnected-(U9-S1D6_M1D5-Pad46)") (class "Default")
      (node (ref "U9") (pin "46") (pinfunction "S1D6_M1D5_46") (pintype "passive+no_connect"))
    )
    (net (code "240") (name "unconnected-(U9-S1D7_M1D4-Pad45)") (class "Default")
      (node (ref "U9") (pin "45") (pinfunction "S1D7_M1D4_45") (pintype "passive+no_connect"))
    )
    (net (code "241") (name "unconnected-(U9-SD1_WP-Pad2)") (class "Default")
      (node (ref "U9") (pin "2") (pinfunction "SD1_WP_2") (pintype "passive+no_connect"))
    )
    (net (code "242") (name "unconnected-(U9-SPI_CK-Pad19)") (class "Default")
      (node (ref "U9") (pin "19") (pinfunction "SPI_CK_19") (pintype "passive+no_connect"))
    )
    (net (code "243") (name "unconnected-(U9-SPI_CS-Pad20)") (class "Default")
      (node (ref "U9") (pin "20") (pinfunction "SPI_CS_20") (pintype "passive+no_connect"))
    )
    (net (code "244") (name "unconnected-(U9-SPI_MISO-Pad17)") (class "Default")
      (node (ref "U9") (pin "17") (pinfunction "SPI_MISO_17") (pintype "passive+no_connect"))
    )
    (net (code "245") (name "unconnected-(U9-SPI_MOSI-Pad18)") (class "Default")
      (node (ref "U9") (pin "18") (pinfunction "SPI_MOSI_18") (pintype "passive+no_connect"))
    )
    (net (code "246") (name "unconnected-(U10-MS2_INS-Pad35)") (class "Default")
      (node (ref "U10") (pin "35") (pinfunction "MS2_INS_35") (pintype "passive+no_connect"))
    )
    (net (code "247") (name "unconnected-(U10-S1D4_M1D7-Pad48)") (class "Default")
      (node (ref "U10") (pin "48") (pinfunction "S1D4_M1D7_48") (pintype "passive+no_connect"))
    )
    (net (code "248") (name "unconnected-(U10-S1D5_M1D6-Pad47)") (class "Default")
      (node (ref "U10") (pin "47") (pinfunction "S1D5_M1D6_47") (pintype "passive+no_connect"))
    )
    (net (code "249") (name "unconnected-(U10-S1D6_M1D5-Pad46)") (class "Default")
      (node (ref "U10") (pin "46") (pinfunction "S1D6_M1D5_46") (pintype "passive+no_connect"))
    )
    (net (code "250") (name "unconnected-(U10-S1D7_M1D4-Pad45)") (class "Default")
      (node (ref "U10") (pin "45") (pinfunction "S1D7_M1D4_45") (pintype "passive+no_connect"))
    )
    (net (code "251") (name "unconnected-(U10-SD1_WP-Pad2)") (class "Default")
      (node (ref "U10") (pin "2") (pinfunction "SD1_WP_2") (pintype "passive+no_connect"))
    )
    (net (code "252") (name "unconnected-(U10-SPI_CK-Pad19)") (class "Default")
      (node (ref "U10") (pin "19") (pinfunction "SPI_CK_19") (pintype "passive+no_connect"))
    )
    (net (code "253") (name "unconnected-(U10-SPI_CS-Pad20)") (class "Default")
      (node (ref "U10") (pin "20") (pinfunction "SPI_CS_20") (pintype "passive+no_connect"))
    )
    (net (code "254") (name "unconnected-(U10-SPI_MISO-Pad17)") (class "Default")
      (node (ref "U10") (pin "17") (pinfunction "SPI_MISO_17") (pintype "passive+no_connect"))
    )
    (net (code "255") (name "unconnected-(U10-SPI_MOSI-Pad18)") (class "Default")
      (node (ref "U10") (pin "18") (pinfunction "SPI_MOSI_18") (pintype "passive+no_connect"))
    )
  )
)
